# DATALOGGER_CA_ADC_V1.net
KiCad netlist of a schematic drawn in EAGLE
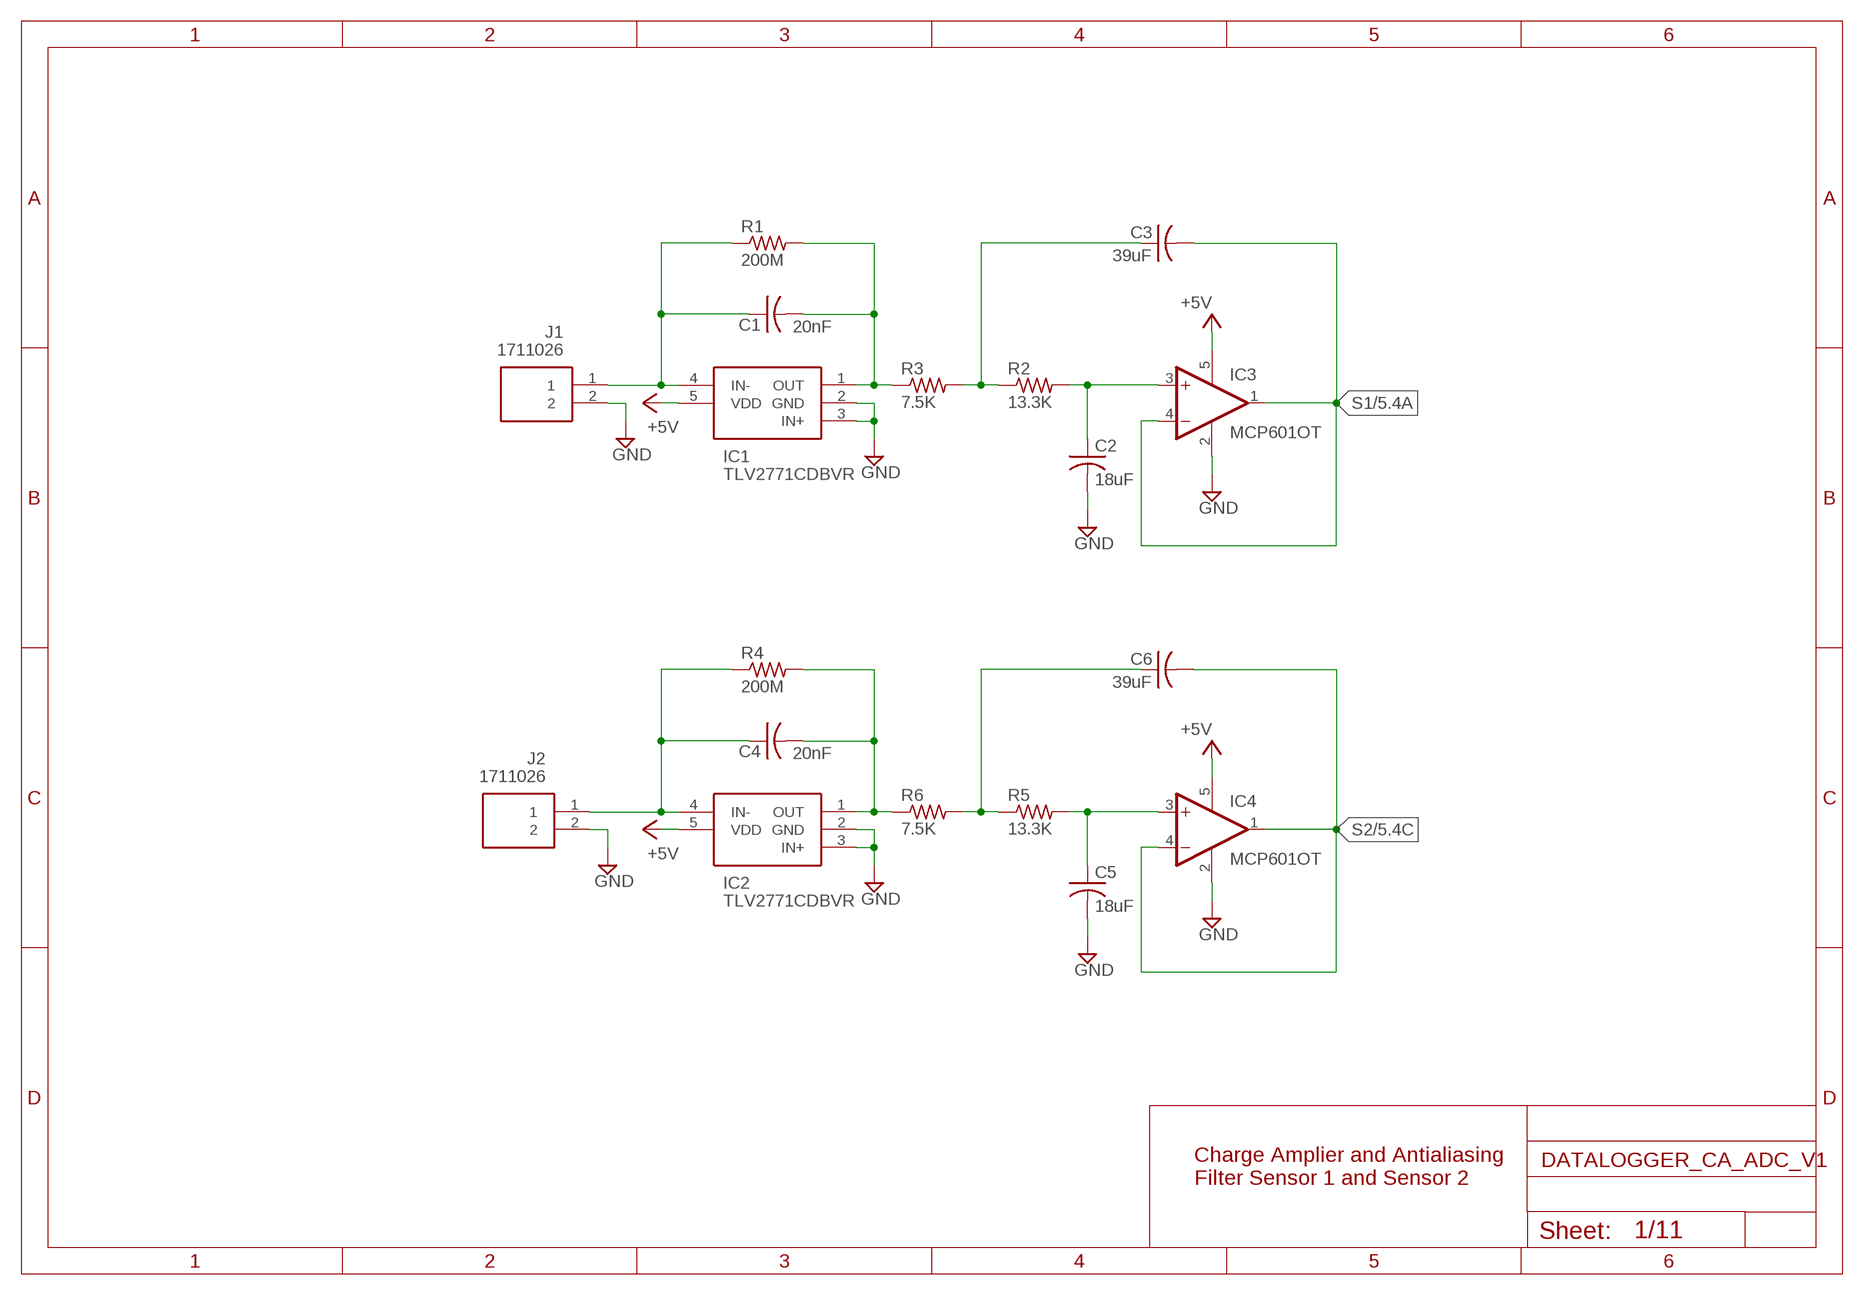
[diagram p0: schematic, sheet 1]
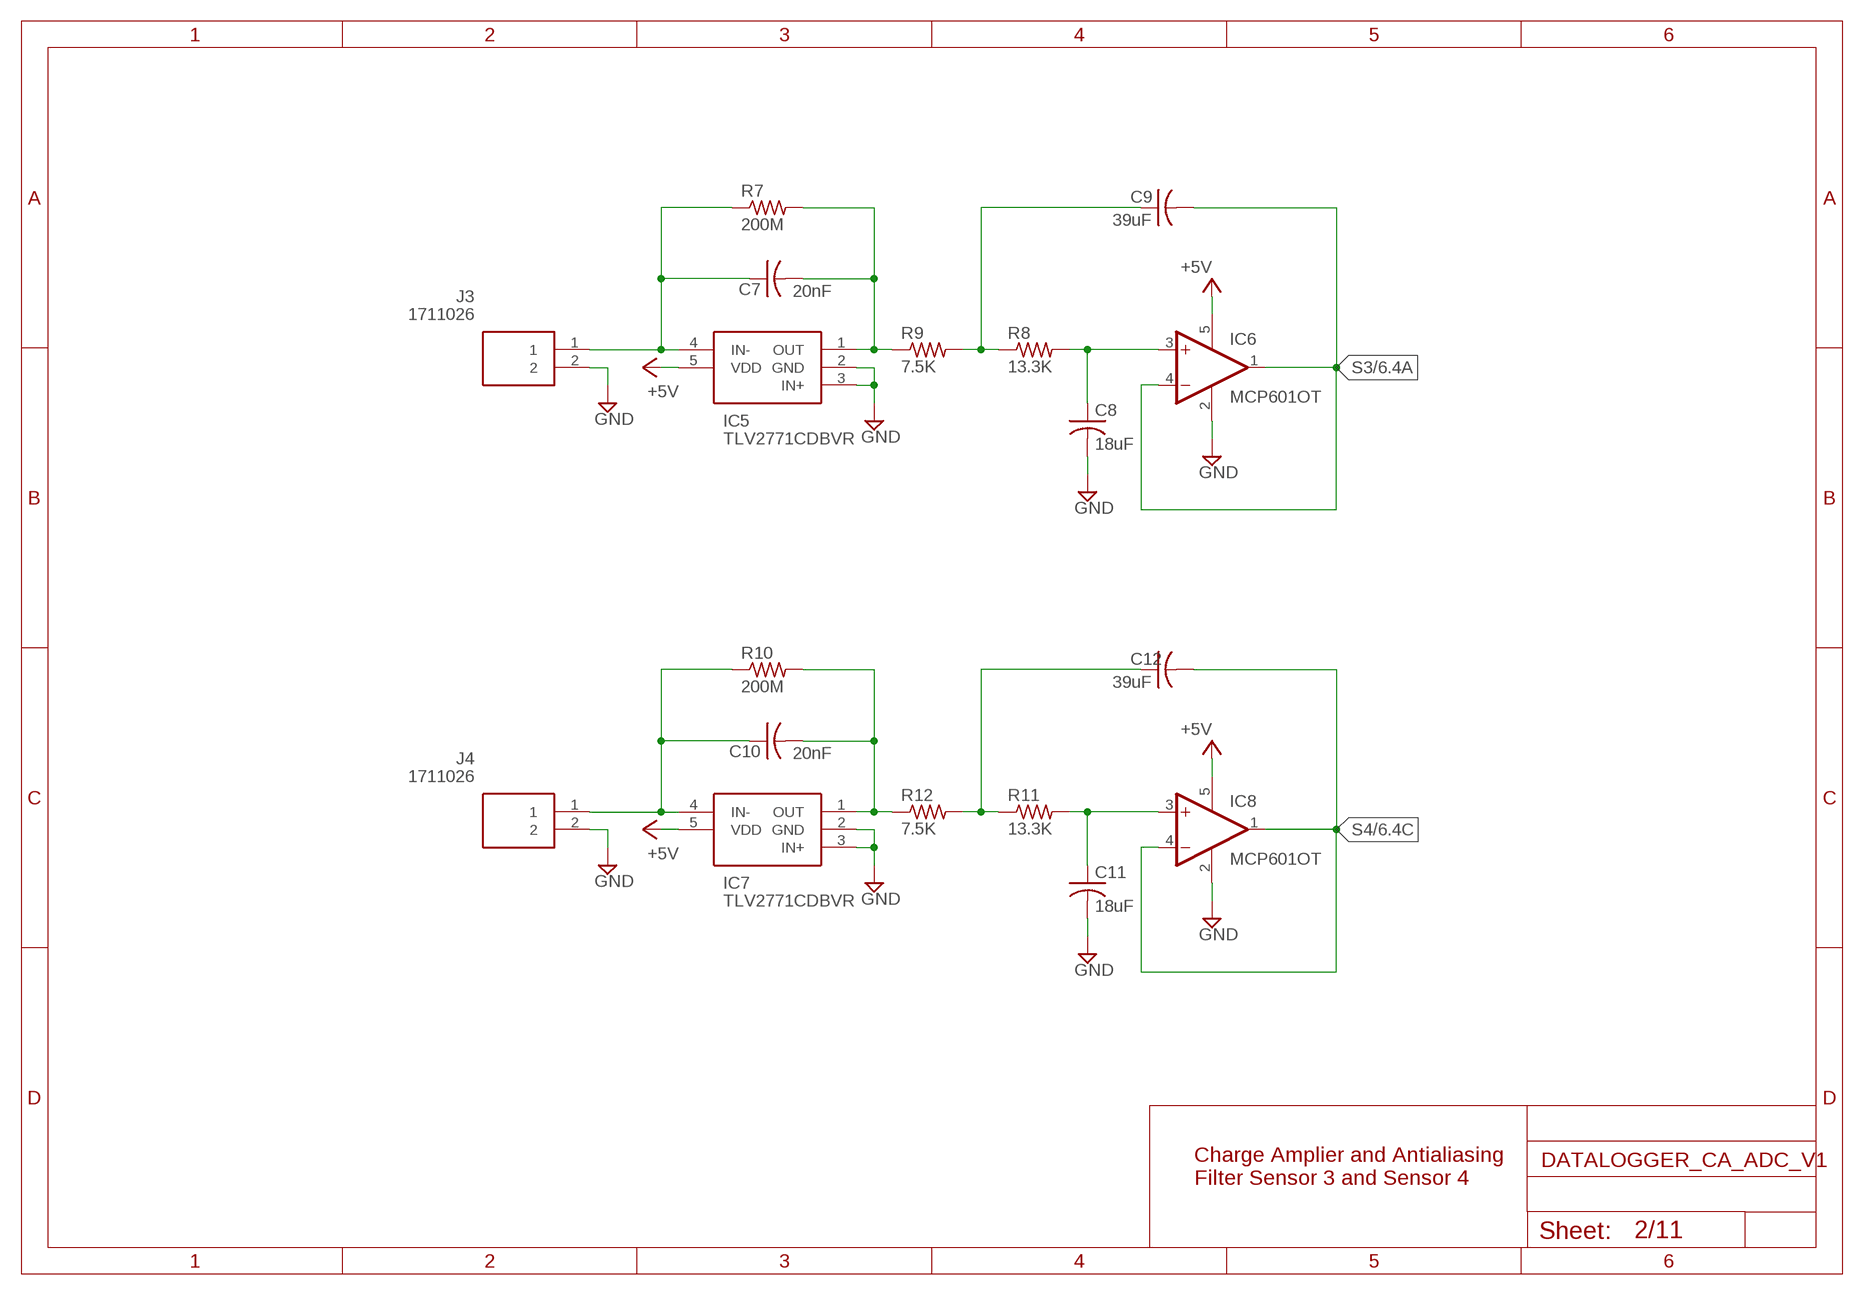
[diagram p1: schematic, sheet 2]
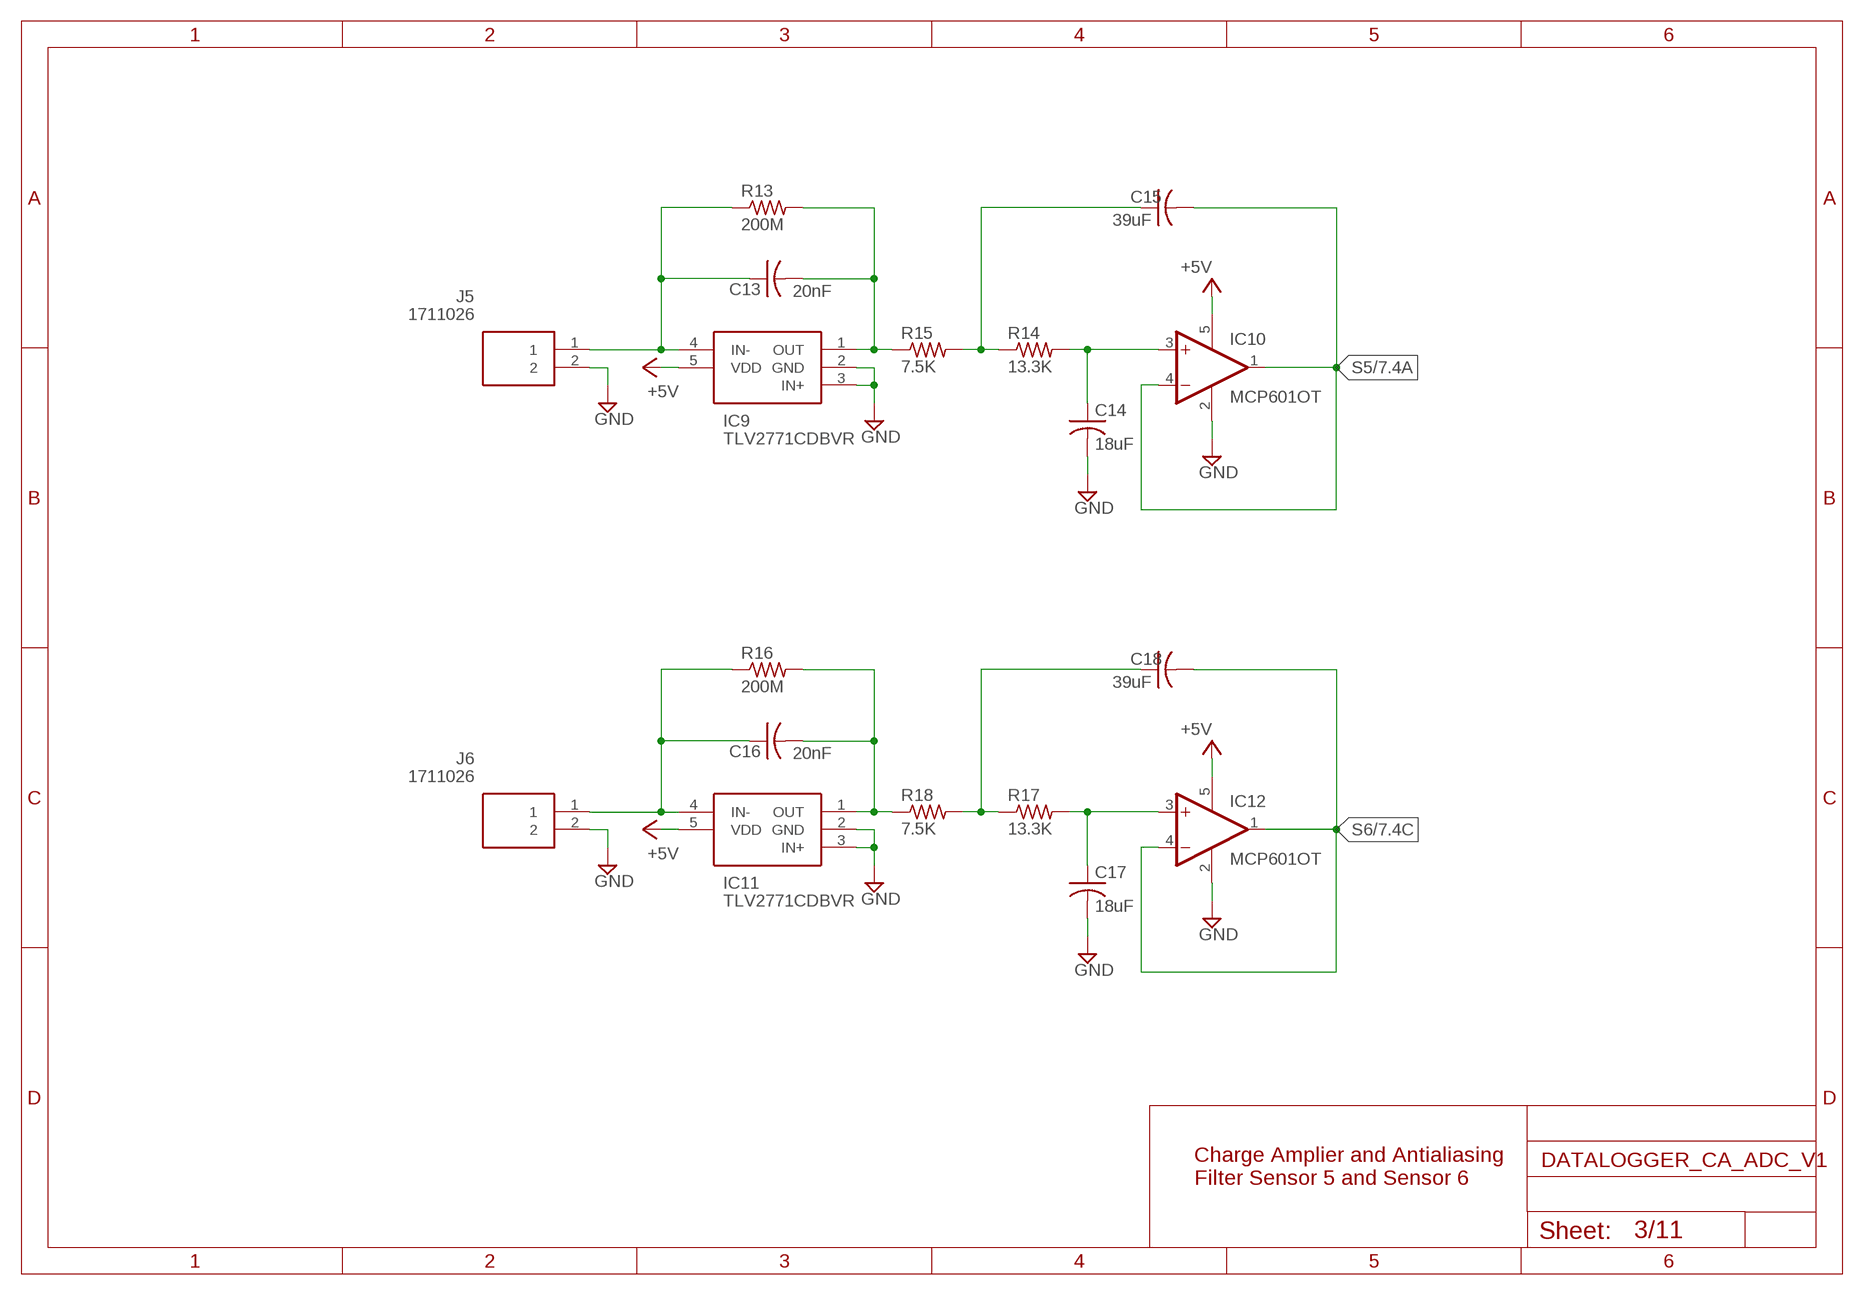
[diagram p2: schematic, sheet 3]
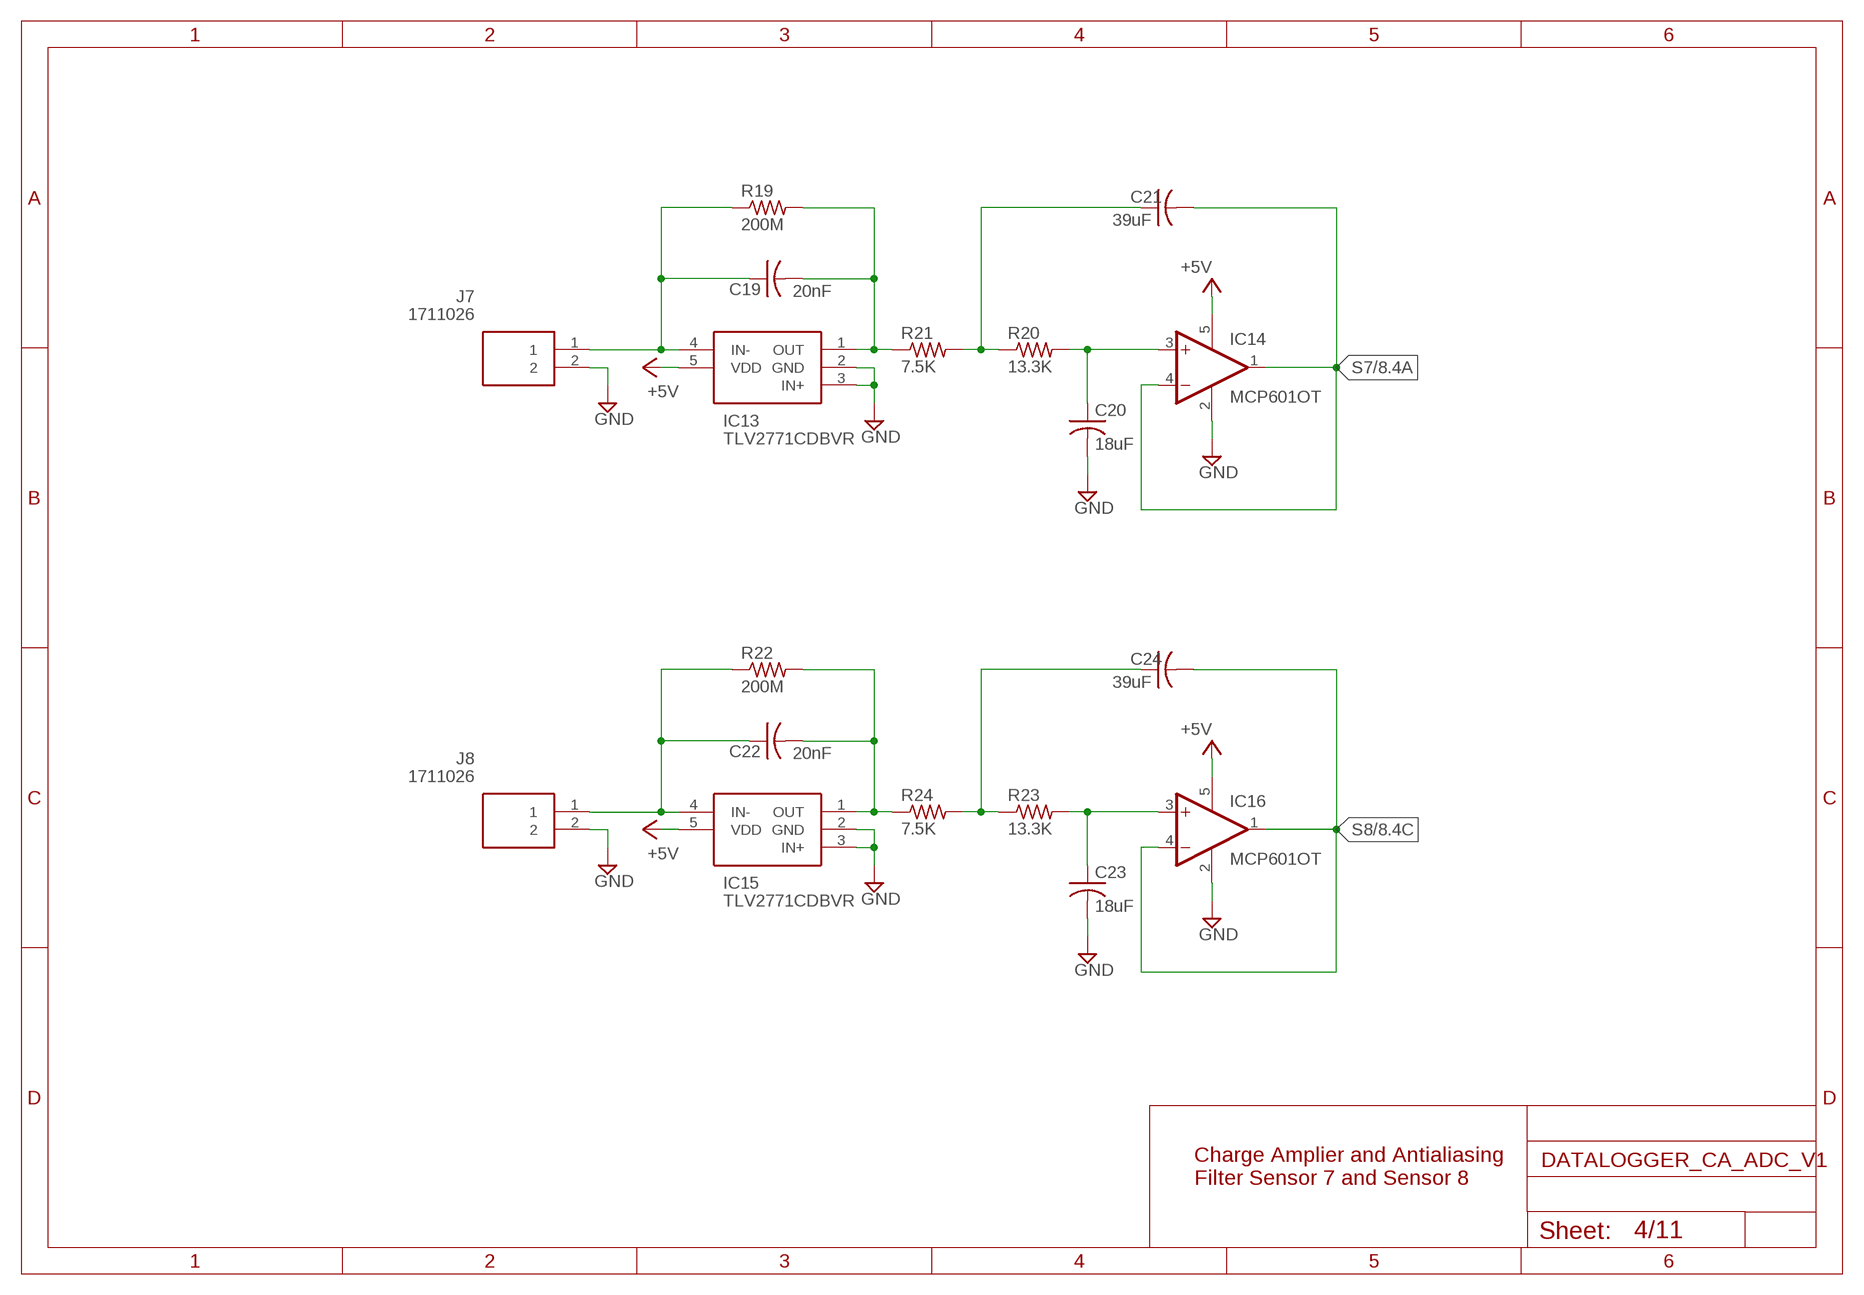
[diagram p3: schematic, sheet 4]
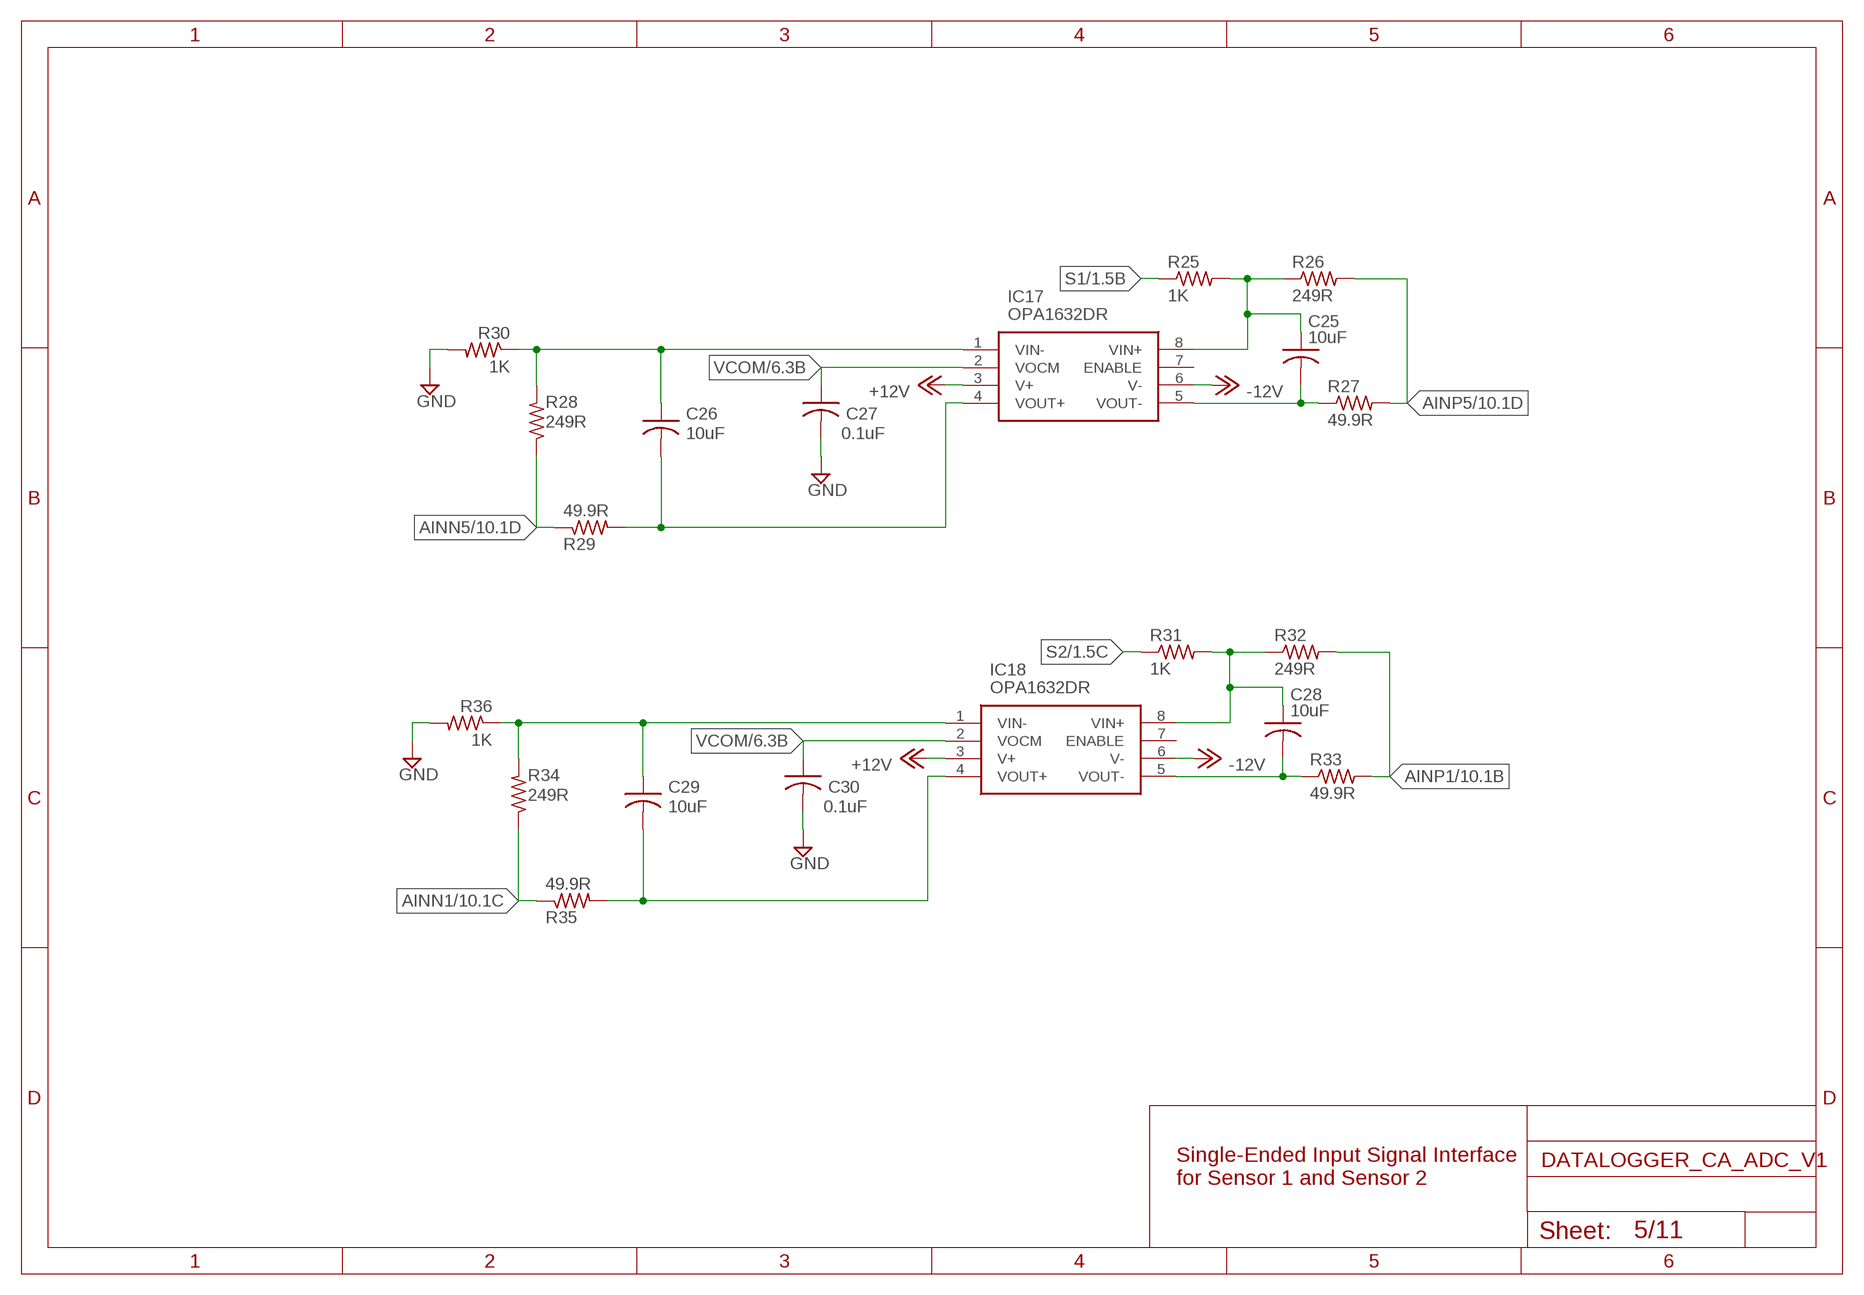
[diagram p4: schematic, sheet 5]
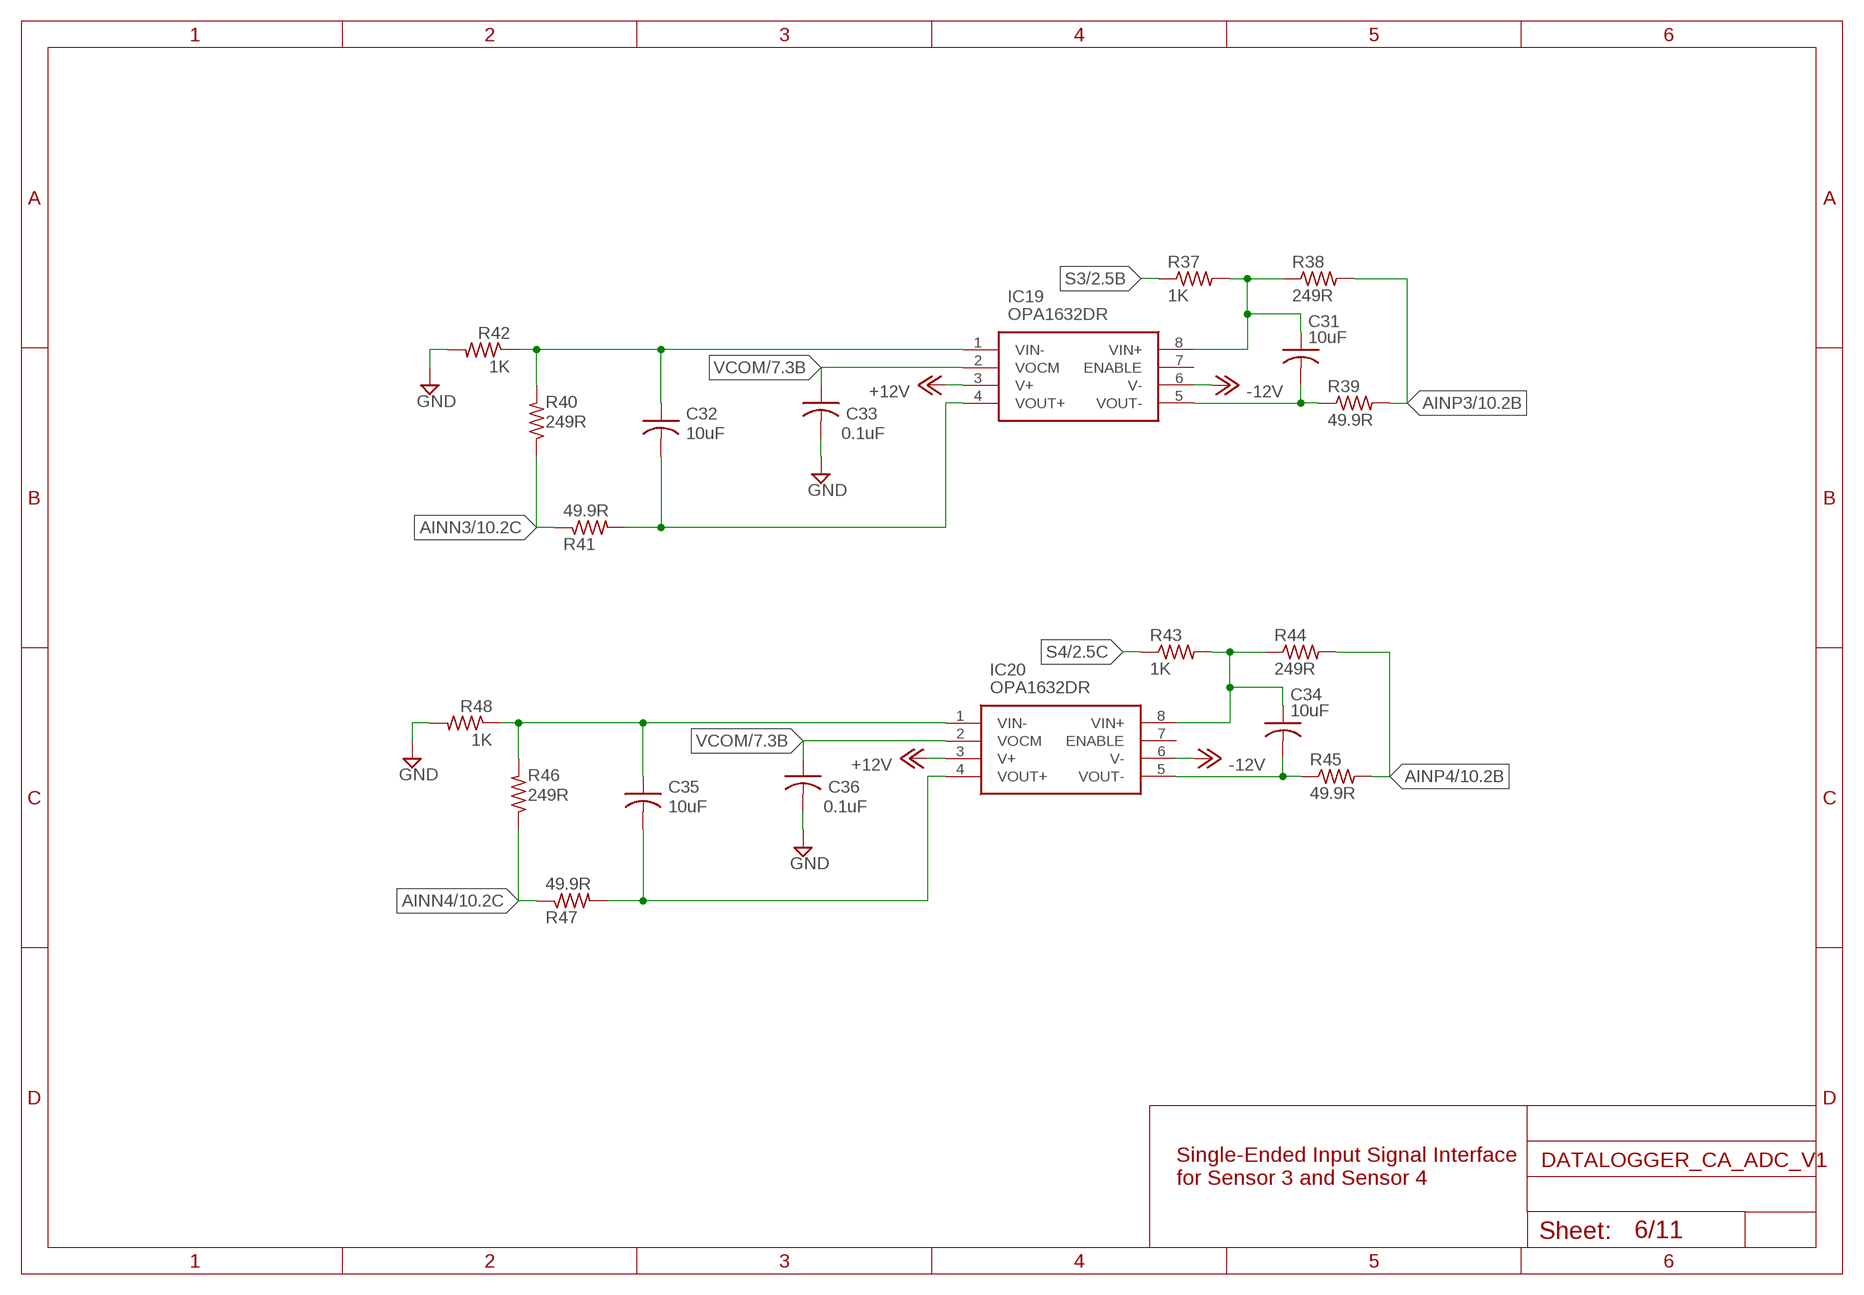
[diagram p5: schematic, sheet 6]
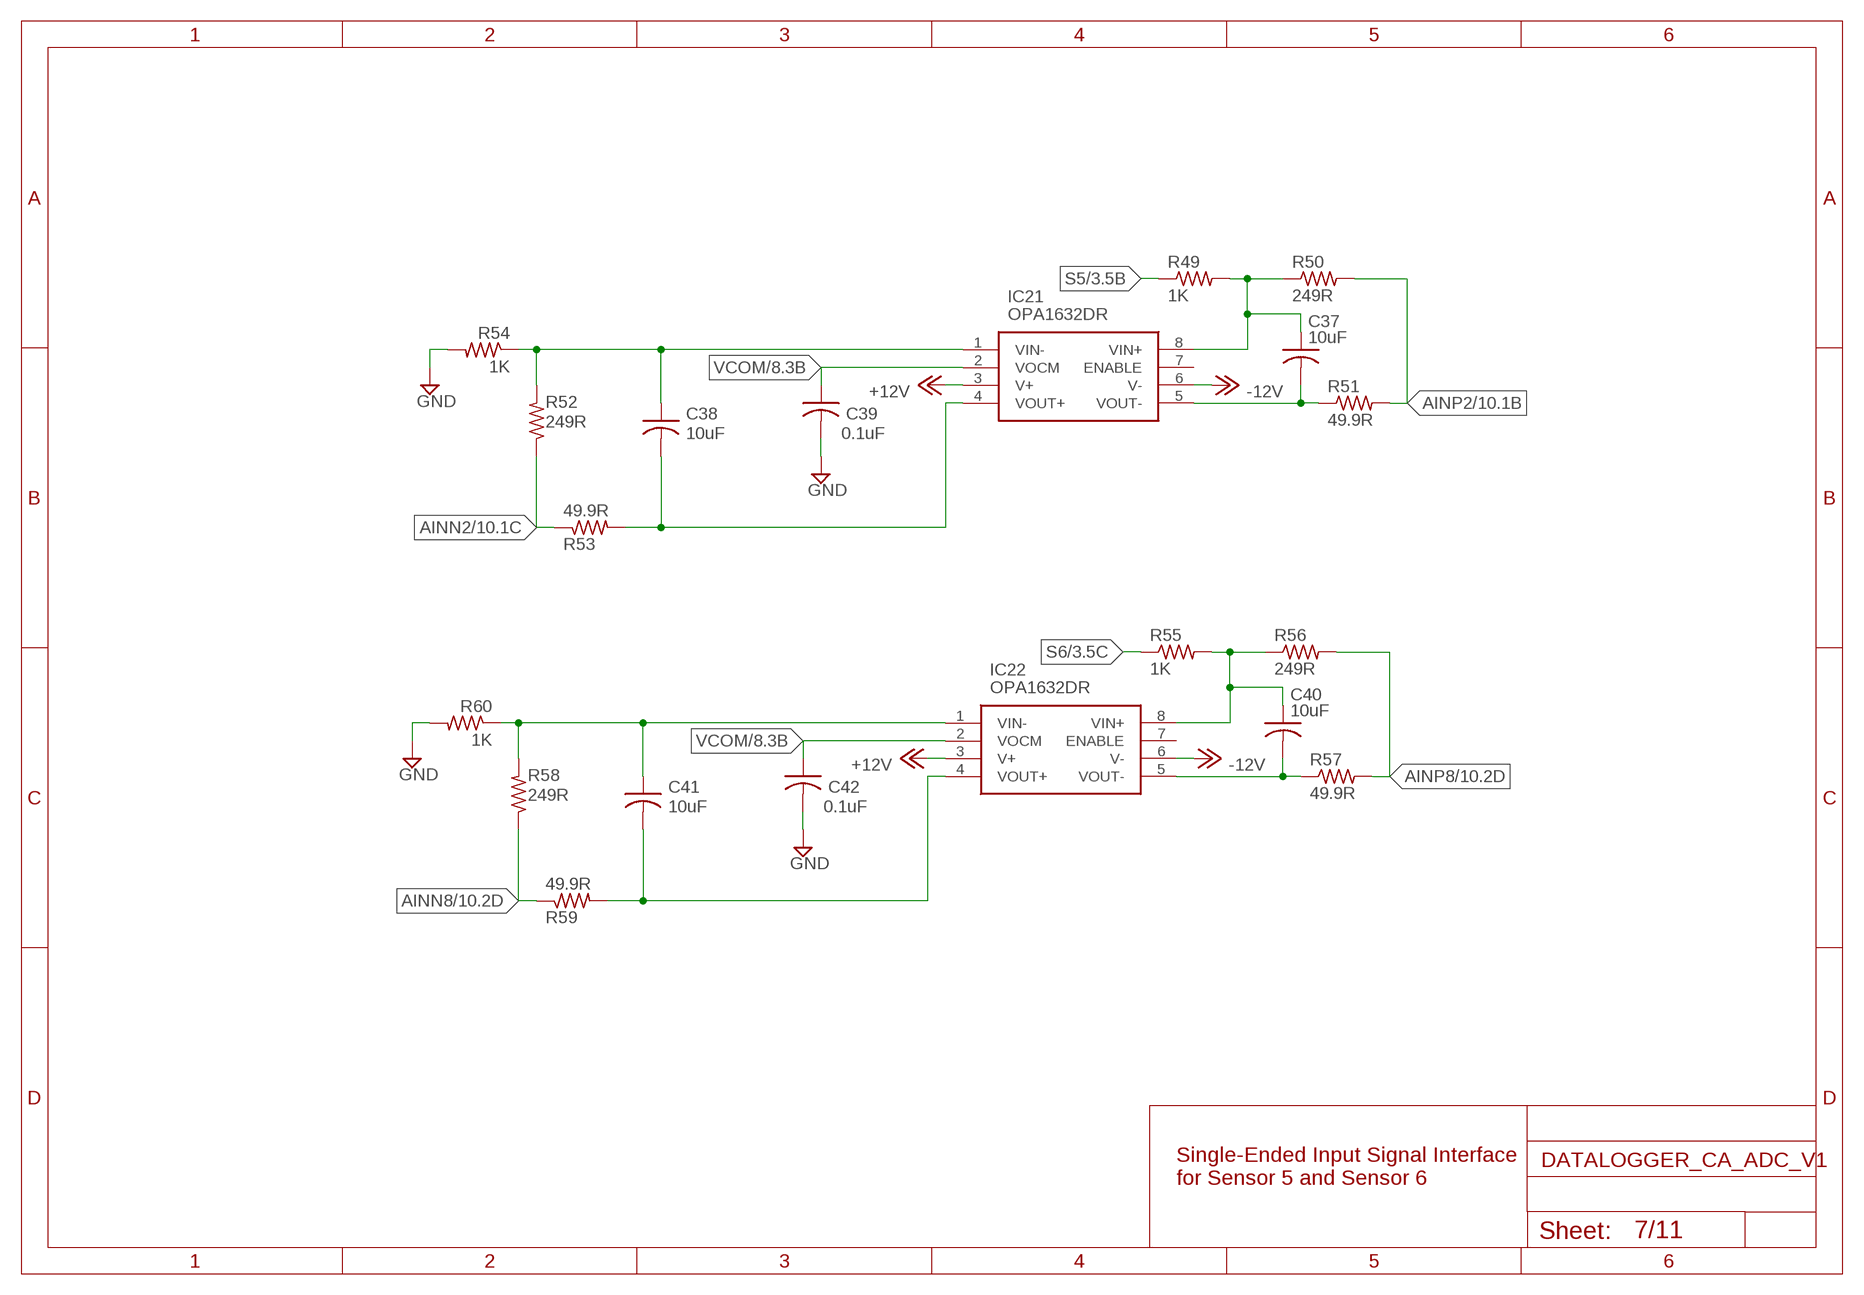
[diagram p6: schematic, sheet 7]
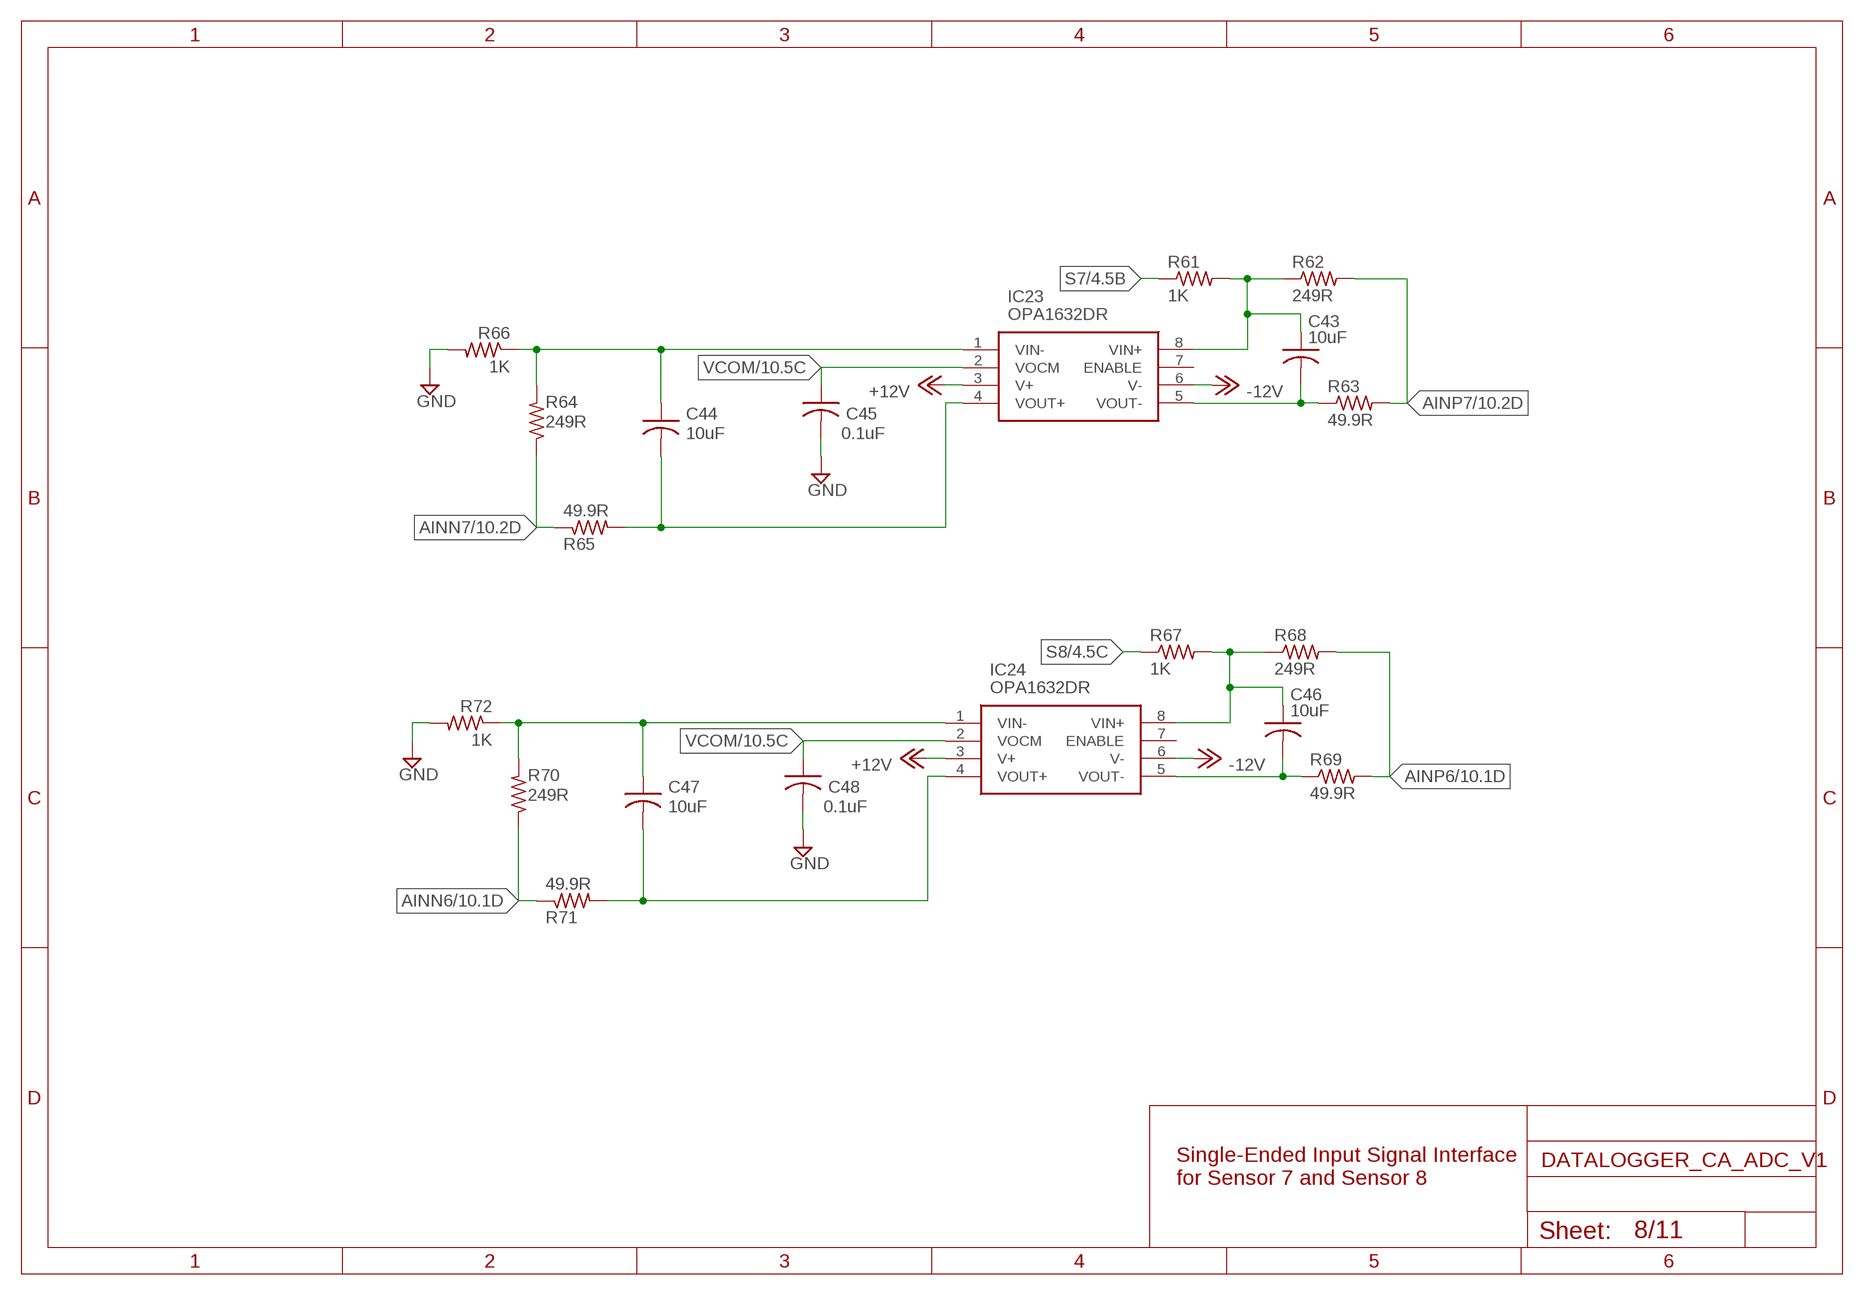
[diagram p7: schematic, sheet 8]
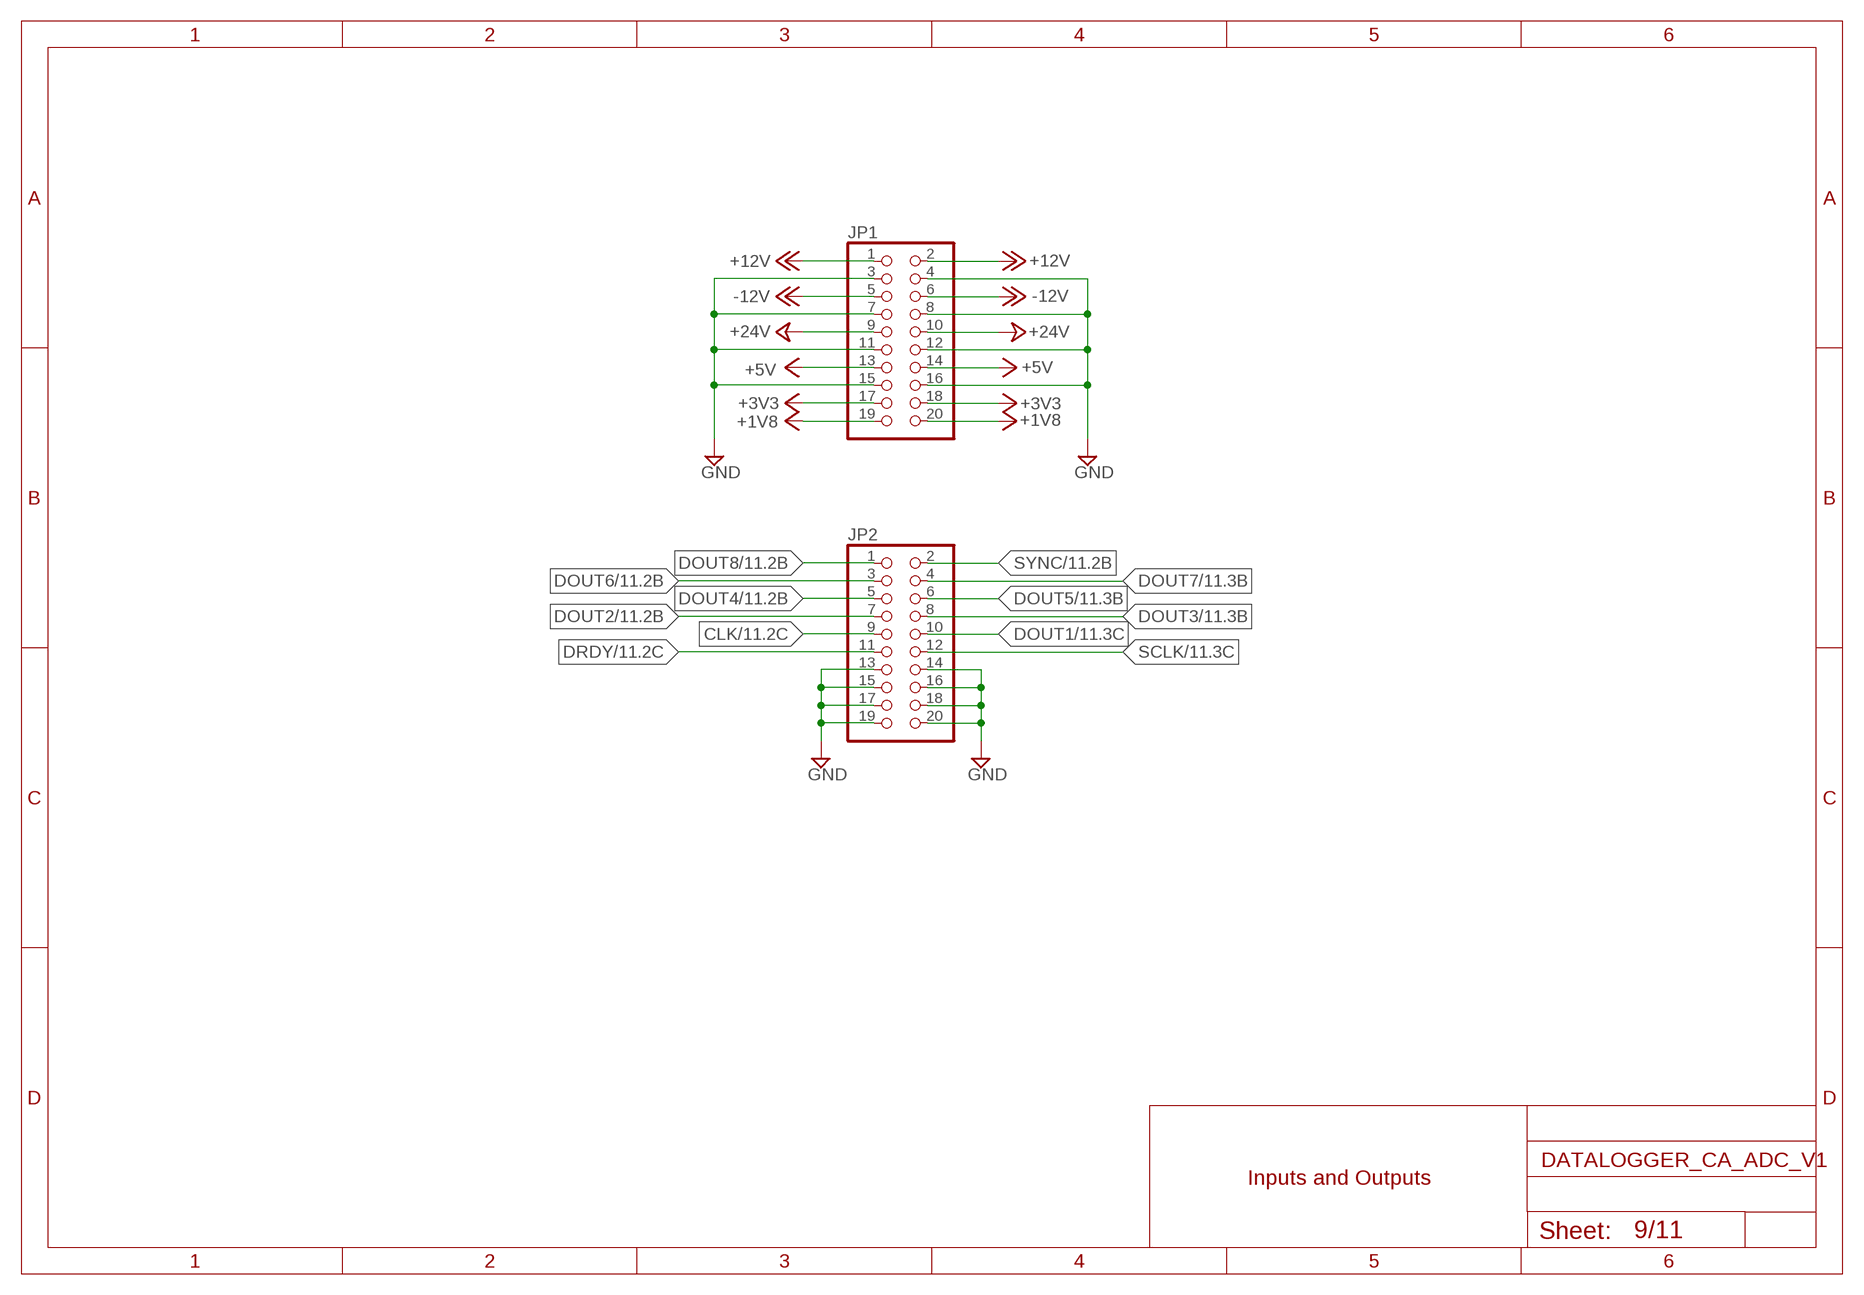
[diagram p8: schematic, sheet 9]
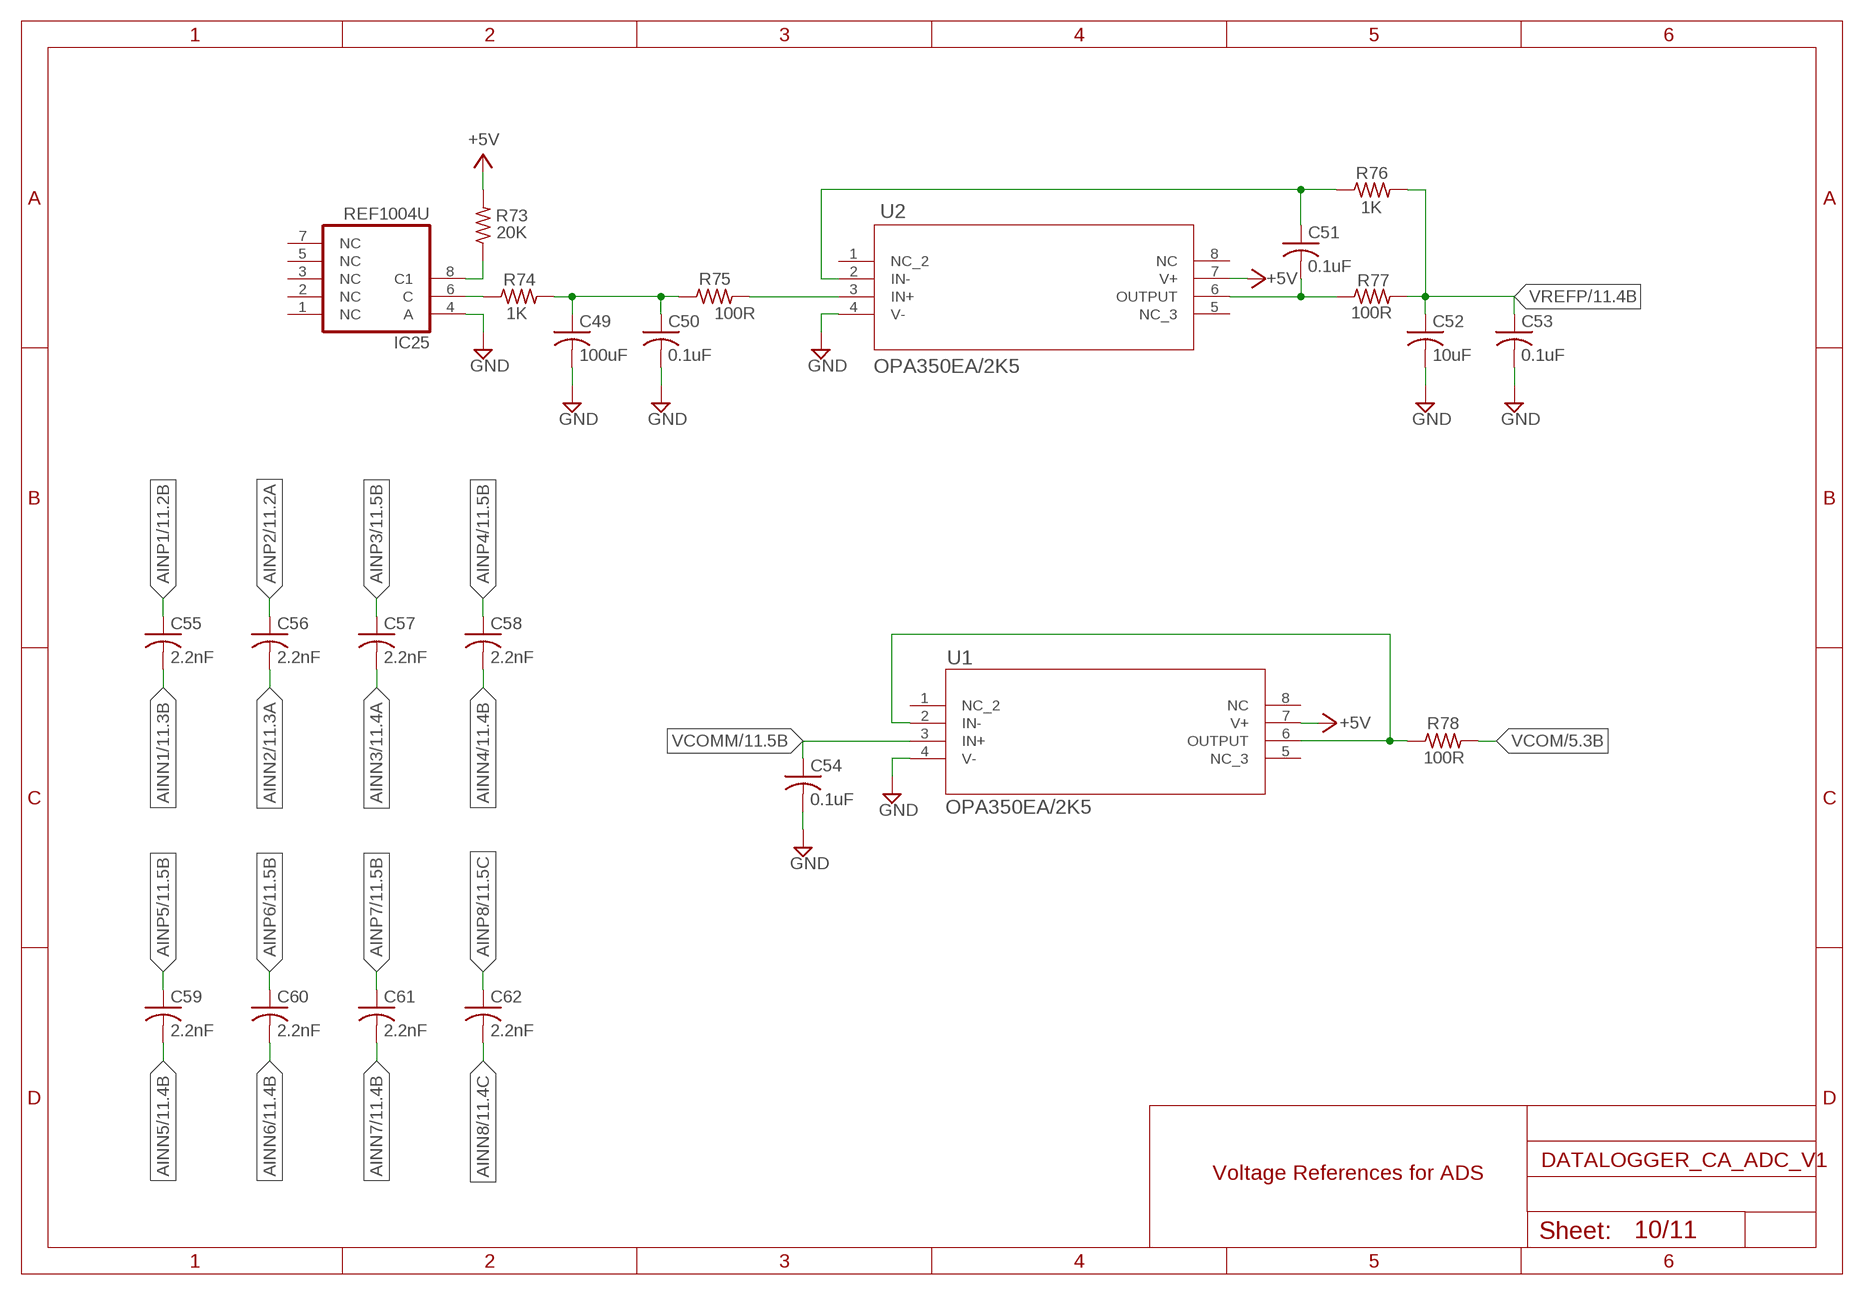
[diagram p9: schematic, sheet 10]
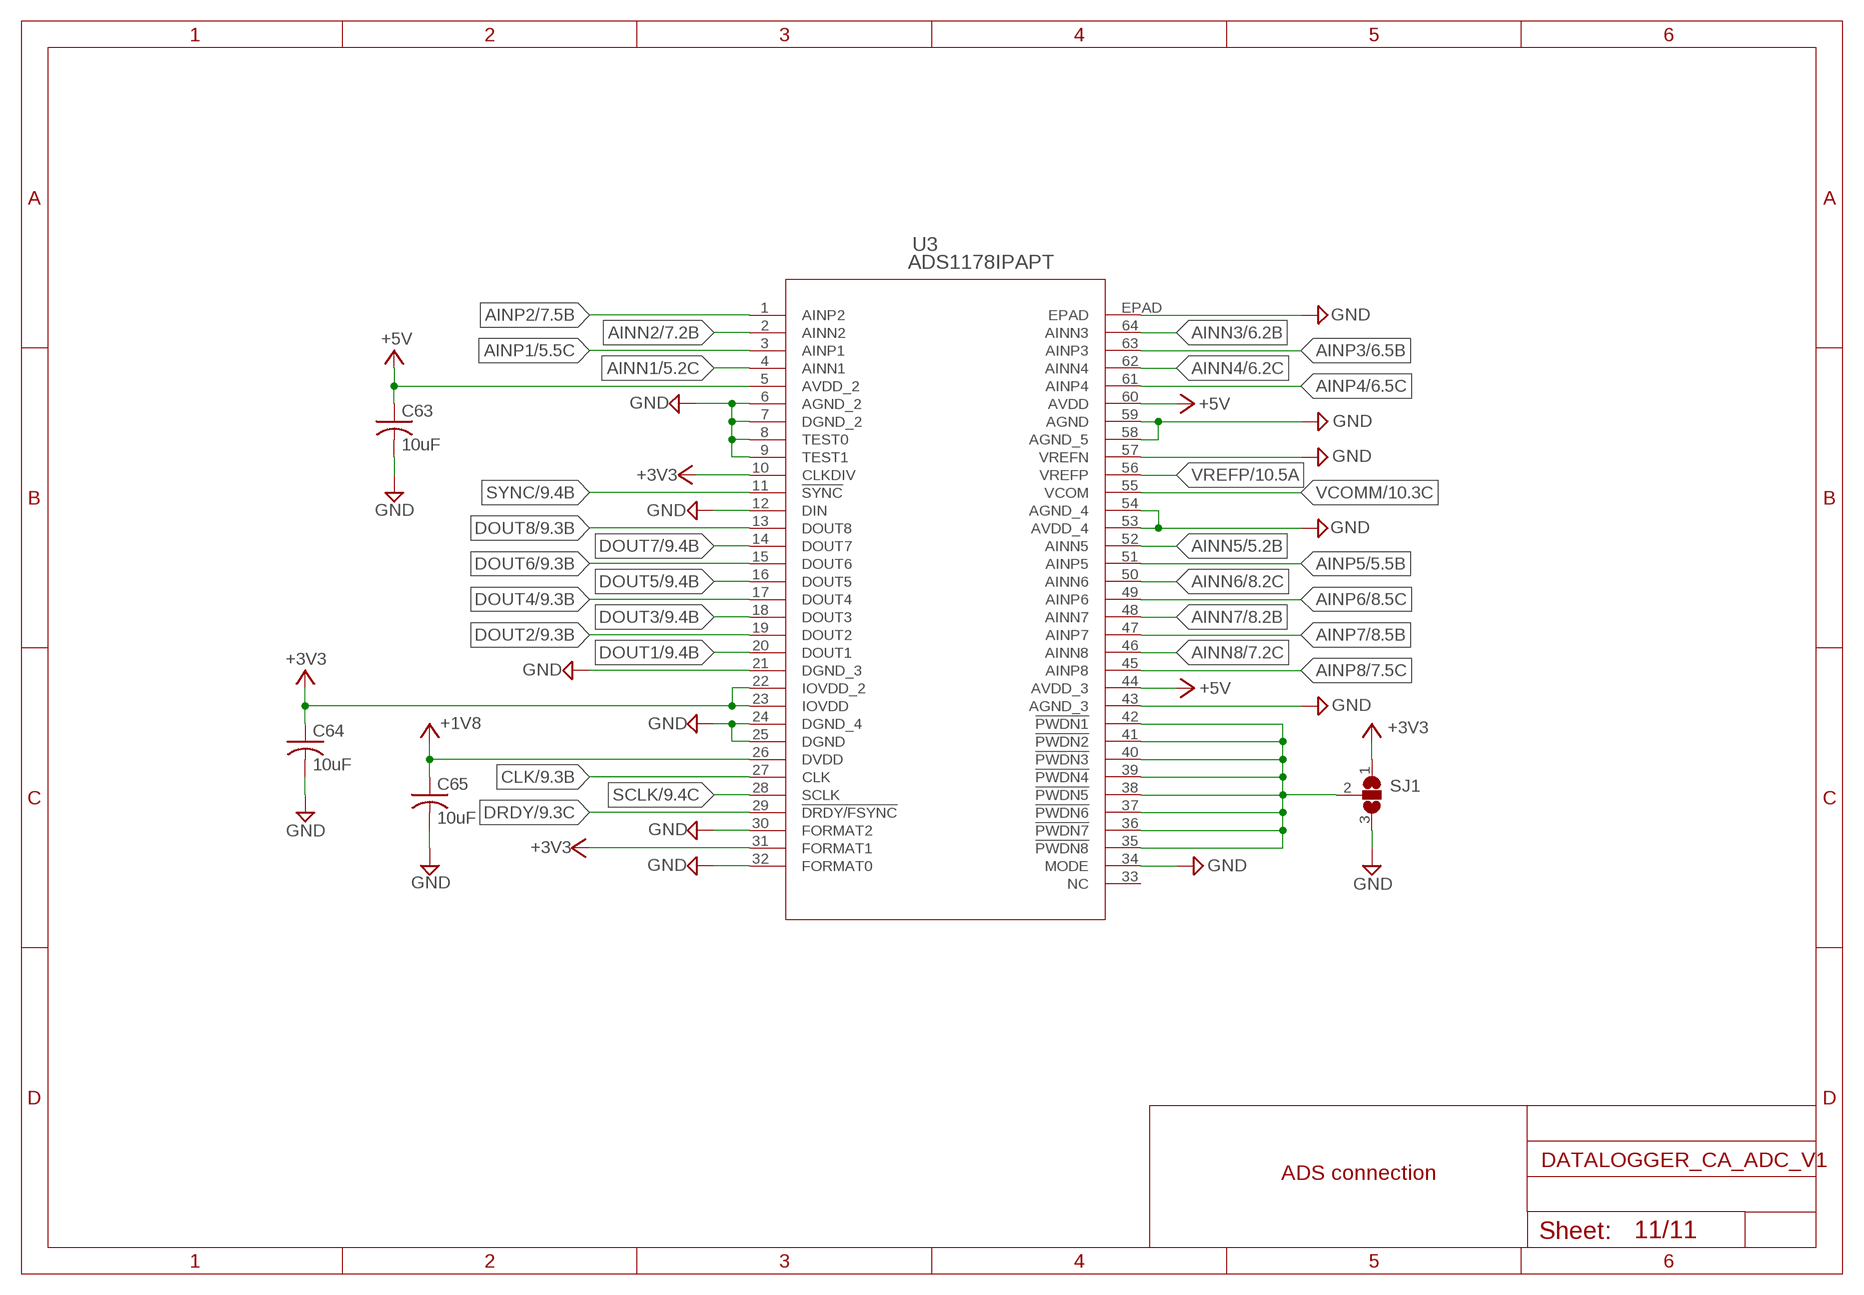
[diagram p10: schematic, sheet 11]

(export (version "E")
  (design (tool "Eeschema 10.0.6"))
  (components
    (comp (ref "C19")
      (value "20nF")
      (footprint "eagle-import:C0805")
      (libsource (lib "eagle-import") (part "C-USC0805"))
    )
    (comp (ref "C20")
      (value "18uF")
      (footprint "eagle-import:C0805")
      (libsource (lib "eagle-import") (part "C-USC0805"))
    )
    (comp (ref "C21")
      (value "39uF")
      (footprint "eagle-import:C0805")
      (libsource (lib "eagle-import") (part "C-USC0805"))
    )
    (comp (ref "C22")
      (value "20nF")
      (footprint "eagle-import:C0805")
      (libsource (lib "eagle-import") (part "C-USC0805"))
    )
    (comp (ref "C23")
      (value "18uF")
      (footprint "eagle-import:C0805")
      (libsource (lib "eagle-import") (part "C-USC0805"))
    )
    (comp (ref "C24")
      (value "39uF")
      (footprint "eagle-import:C0805")
      (libsource (lib "eagle-import") (part "C-USC0805"))
    )
    (comp (ref "IC13")
      (value "TLV2771CDBVR")
      (footprint "eagle-import:SOT95P280X145-5N")
      (fields (field (name "MOUSER_PART_NUMBER") "595-TLV2771CDBVR"))
      (libsource (lib "eagle-import") (part "TLV2771CDBVR"))
    )
    (comp (ref "IC14")
      (value "MCP601OT")
      (footprint "eagle-import:SOT23-5")
      (libsource (lib "eagle-import") (part "MCP601OT"))
    )
    (comp (ref "IC15")
      (value "TLV2771CDBVR")
      (footprint "eagle-import:SOT95P280X145-5N")
      (fields (field (name "MOUSER_PART_NUMBER") "595-TLV2771CDBVR"))
      (libsource (lib "eagle-import") (part "TLV2771CDBVR"))
    )
    (comp (ref "IC16")
      (value "MCP601OT")
      (footprint "eagle-import:SOT23-5")
      (libsource (lib "eagle-import") (part "MCP601OT"))
    )
    (comp (ref "J7")
      (value "1711026")
      (footprint "eagle-import:SHDR2W110P0X500_1X2_1000X1120X")
      (fields (field (name "MOUSER_PART_NUMBER") "651-1711026"))
      (libsource (lib "eagle-import") (part "1711026"))
    )
    (comp (ref "J8")
      (value "1711026")
      (footprint "eagle-import:SHDR2W110P0X500_1X2_1000X1120X")
      (fields (field (name "MOUSER_PART_NUMBER") "651-1711026"))
      (libsource (lib "eagle-import") (part "1711026"))
    )
    (comp (ref "R19")
      (value "200M")
      (footprint "eagle-import:R0805")
      (libsource (lib "eagle-import") (part "R-US_R0805"))
    )
    (comp (ref "R20")
      (value "13.3K")
      (footprint "eagle-import:R0805")
      (libsource (lib "eagle-import") (part "R-US_R0805"))
    )
    (comp (ref "R21")
      (value "7.5K")
      (footprint "eagle-import:R0805")
      (libsource (lib "eagle-import") (part "R-US_R0805"))
    )
    (comp (ref "R22")
      (value "200M")
      (footprint "eagle-import:R0805")
      (libsource (lib "eagle-import") (part "R-US_R0805"))
    )
    (comp (ref "R23")
      (value "13.3K")
      (footprint "eagle-import:R0805")
      (libsource (lib "eagle-import") (part "R-US_R0805"))
    )
    (comp (ref "R24")
      (value "7.5K")
      (footprint "eagle-import:R0805")
      (libsource (lib "eagle-import") (part "R-US_R0805"))
    )
    (comp (ref "C37")
      (value "10uF")
      (footprint "eagle-import:C0805")
      (libsource (lib "eagle-import") (part "C-USC0805"))
    )
    (comp (ref "C38")
      (value "10uF")
      (footprint "eagle-import:C0805")
      (libsource (lib "eagle-import") (part "C-USC0805"))
    )
    (comp (ref "C39")
      (value "0.1uF")
      (footprint "eagle-import:C0805")
      (libsource (lib "eagle-import") (part "C-USC0805"))
    )
    (comp (ref "C40")
      (value "10uF")
      (footprint "eagle-import:C0805")
      (libsource (lib "eagle-import") (part "C-USC0805"))
    )
    (comp (ref "C41")
      (value "10uF")
      (footprint "eagle-import:C0805")
      (libsource (lib "eagle-import") (part "C-USC0805"))
    )
    (comp (ref "C42")
      (value "0.1uF")
      (footprint "eagle-import:C0805")
      (libsource (lib "eagle-import") (part "C-USC0805"))
    )
    (comp (ref "IC21")
      (value "OPA1632DR")
      (footprint "eagle-import:SOIC127P600X175-8N")
      (fields (field (name "MOUSER_PART_NUMBER") "595-OPA1632DR"))
      (libsource (lib "eagle-import") (part "OPA1632DR"))
    )
    (comp (ref "IC22")
      (value "OPA1632DR")
      (footprint "eagle-import:SOIC127P600X175-8N")
      (fields (field (name "MOUSER_PART_NUMBER") "595-OPA1632DR"))
      (libsource (lib "eagle-import") (part "OPA1632DR"))
    )
    (comp (ref "R49")
      (value "1K")
      (footprint "eagle-import:R0805")
      (libsource (lib "eagle-import") (part "R-US_R0805"))
    )
    (comp (ref "R50")
      (value "249R")
      (footprint "eagle-import:R0805")
      (libsource (lib "eagle-import") (part "R-US_R0805"))
    )
    (comp (ref "R51")
      (value "49.9R")
      (footprint "eagle-import:R0805")
      (libsource (lib "eagle-import") (part "R-US_R0805"))
    )
    (comp (ref "R52")
      (value "249R")
      (footprint "eagle-import:R0805")
      (libsource (lib "eagle-import") (part "R-US_R0805"))
    )
    (comp (ref "R53")
      (value "49.9R")
      (footprint "eagle-import:R0805")
      (libsource (lib "eagle-import") (part "R-US_R0805"))
    )
    (comp (ref "R54")
      (value "1K")
      (footprint "eagle-import:R0805")
      (libsource (lib "eagle-import") (part "R-US_R0805"))
    )
    (comp (ref "R55")
      (value "1K")
      (footprint "eagle-import:R0805")
      (libsource (lib "eagle-import") (part "R-US_R0805"))
    )
    (comp (ref "R56")
      (value "249R")
      (footprint "eagle-import:R0805")
      (libsource (lib "eagle-import") (part "R-US_R0805"))
    )
    (comp (ref "R57")
      (value "49.9R")
      (footprint "eagle-import:R0805")
      (libsource (lib "eagle-import") (part "R-US_R0805"))
    )
    (comp (ref "R58")
      (value "249R")
      (footprint "eagle-import:R0805")
      (libsource (lib "eagle-import") (part "R-US_R0805"))
    )
    (comp (ref "R59")
      (value "49.9R")
      (footprint "eagle-import:R0805")
      (libsource (lib "eagle-import") (part "R-US_R0805"))
    )
    (comp (ref "R60")
      (value "1K")
      (footprint "eagle-import:R0805")
      (libsource (lib "eagle-import") (part "R-US_R0805"))
    )
    (comp (ref "C7")
      (value "20nF")
      (footprint "eagle-import:C0805")
      (libsource (lib "eagle-import") (part "C-USC0805"))
    )
    (comp (ref "C8")
      (value "18uF")
      (footprint "eagle-import:C0805")
      (libsource (lib "eagle-import") (part "C-USC0805"))
    )
    (comp (ref "C9")
      (value "39uF")
      (footprint "eagle-import:C0805")
      (libsource (lib "eagle-import") (part "C-USC0805"))
    )
    (comp (ref "C10")
      (value "20nF")
      (footprint "eagle-import:C0805")
      (libsource (lib "eagle-import") (part "C-USC0805"))
    )
    (comp (ref "C11")
      (value "18uF")
      (footprint "eagle-import:C0805")
      (libsource (lib "eagle-import") (part "C-USC0805"))
    )
    (comp (ref "C12")
      (value "39uF")
      (footprint "eagle-import:C0805")
      (libsource (lib "eagle-import") (part "C-USC0805"))
    )
    (comp (ref "IC5")
      (value "TLV2771CDBVR")
      (footprint "eagle-import:SOT95P280X145-5N")
      (fields (field (name "MOUSER_PART_NUMBER") "595-TLV2771CDBVR"))
      (libsource (lib "eagle-import") (part "TLV2771CDBVR"))
    )
    (comp (ref "IC6")
      (value "MCP601OT")
      (footprint "eagle-import:SOT23-5")
      (libsource (lib "eagle-import") (part "MCP601OT"))
    )
    (comp (ref "IC7")
      (value "TLV2771CDBVR")
      (footprint "eagle-import:SOT95P280X145-5N")
      (fields (field (name "MOUSER_PART_NUMBER") "595-TLV2771CDBVR"))
      (libsource (lib "eagle-import") (part "TLV2771CDBVR"))
    )
    (comp (ref "IC8")
      (value "MCP601OT")
      (footprint "eagle-import:SOT23-5")
      (libsource (lib "eagle-import") (part "MCP601OT"))
    )
    (comp (ref "J3")
      (value "1711026")
      (footprint "eagle-import:SHDR2W110P0X500_1X2_1000X1120X")
      (fields (field (name "MOUSER_PART_NUMBER") "651-1711026"))
      (libsource (lib "eagle-import") (part "1711026"))
    )
    (comp (ref "J4")
      (value "1711026")
      (footprint "eagle-import:SHDR2W110P0X500_1X2_1000X1120X")
      (fields (field (name "MOUSER_PART_NUMBER") "651-1711026"))
      (libsource (lib "eagle-import") (part "1711026"))
    )
    (comp (ref "R7")
      (value "200M")
      (footprint "eagle-import:R0805")
      (libsource (lib "eagle-import") (part "R-US_R0805"))
    )
    (comp (ref "R8")
      (value "13.3K")
      (footprint "eagle-import:R0805")
      (libsource (lib "eagle-import") (part "R-US_R0805"))
    )
    (comp (ref "R9")
      (value "7.5K")
      (footprint "eagle-import:R0805")
      (libsource (lib "eagle-import") (part "R-US_R0805"))
    )
    (comp (ref "R10")
      (value "200M")
      (footprint "eagle-import:R0805")
      (libsource (lib "eagle-import") (part "R-US_R0805"))
    )
    (comp (ref "R11")
      (value "13.3K")
      (footprint "eagle-import:R0805")
      (libsource (lib "eagle-import") (part "R-US_R0805"))
    )
    (comp (ref "R12")
      (value "7.5K")
      (footprint "eagle-import:R0805")
      (libsource (lib "eagle-import") (part "R-US_R0805"))
    )
    (comp (ref "C25")
      (value "10uF")
      (footprint "eagle-import:C0805")
      (libsource (lib "eagle-import") (part "C-USC0805"))
    )
    (comp (ref "C26")
      (value "10uF")
      (footprint "eagle-import:C0805")
      (libsource (lib "eagle-import") (part "C-USC0805"))
    )
    (comp (ref "C27")
      (value "0.1uF")
      (footprint "eagle-import:C0805")
      (libsource (lib "eagle-import") (part "C-USC0805"))
    )
    (comp (ref "C28")
      (value "10uF")
      (footprint "eagle-import:C0805")
      (libsource (lib "eagle-import") (part "C-USC0805"))
    )
    (comp (ref "C29")
      (value "10uF")
      (footprint "eagle-import:C0805")
      (libsource (lib "eagle-import") (part "C-USC0805"))
    )
    (comp (ref "C30")
      (value "0.1uF")
      (footprint "eagle-import:C0805")
      (libsource (lib "eagle-import") (part "C-USC0805"))
    )
    (comp (ref "IC17")
      (value "OPA1632DR")
      (footprint "eagle-import:SOIC127P600X175-8N")
      (fields (field (name "MOUSER_PART_NUMBER") "595-OPA1632DR"))
      (libsource (lib "eagle-import") (part "OPA1632DR"))
    )
    (comp (ref "IC18")
      (value "OPA1632DR")
      (footprint "eagle-import:SOIC127P600X175-8N")
      (fields (field (name "MOUSER_PART_NUMBER") "595-OPA1632DR"))
      (libsource (lib "eagle-import") (part "OPA1632DR"))
    )
    (comp (ref "R25")
      (value "1K")
      (footprint "eagle-import:R0805")
      (libsource (lib "eagle-import") (part "R-US_R0805"))
    )
    (comp (ref "R26")
      (value "249R")
      (footprint "eagle-import:R0805")
      (libsource (lib "eagle-import") (part "R-US_R0805"))
    )
    (comp (ref "R27")
      (value "49.9R")
      (footprint "eagle-import:R0805")
      (libsource (lib "eagle-import") (part "R-US_R0805"))
    )
    (comp (ref "R28")
      (value "249R")
      (footprint "eagle-import:R0805")
      (libsource (lib "eagle-import") (part "R-US_R0805"))
    )
    (comp (ref "R29")
      (value "49.9R")
      (footprint "eagle-import:R0805")
      (libsource (lib "eagle-import") (part "R-US_R0805"))
    )
    (comp (ref "R30")
      (value "1K")
      (footprint "eagle-import:R0805")
      (libsource (lib "eagle-import") (part "R-US_R0805"))
    )
    (comp (ref "R31")
      (value "1K")
      (footprint "eagle-import:R0805")
      (libsource (lib "eagle-import") (part "R-US_R0805"))
    )
    (comp (ref "R32")
      (value "249R")
      (footprint "eagle-import:R0805")
      (libsource (lib "eagle-import") (part "R-US_R0805"))
    )
    (comp (ref "R33")
      (value "49.9R")
      (footprint "eagle-import:R0805")
      (libsource (lib "eagle-import") (part "R-US_R0805"))
    )
    (comp (ref "R34")
      (value "249R")
      (footprint "eagle-import:R0805")
      (libsource (lib "eagle-import") (part "R-US_R0805"))
    )
    (comp (ref "R35")
      (value "49.9R")
      (footprint "eagle-import:R0805")
      (libsource (lib "eagle-import") (part "R-US_R0805"))
    )
    (comp (ref "R36")
      (value "1K")
      (footprint "eagle-import:R0805")
      (libsource (lib "eagle-import") (part "R-US_R0805"))
    )
    (comp (ref "C63")
      (value "10uF")
      (footprint "eagle-import:C0805")
      (libsource (lib "eagle-import") (part "C-USC0805"))
    )
    (comp (ref "C64")
      (value "10uF")
      (footprint "eagle-import:C0805")
      (libsource (lib "eagle-import") (part "C-USC0805"))
    )
    (comp (ref "C65")
      (value "10uF")
      (footprint "eagle-import:C0805")
      (libsource (lib "eagle-import") (part "C-USC0805"))
    )
    (comp (ref "SJ1")
      (value "SJ2W")
      (footprint "eagle-import:SJ_2")
      (libsource (lib "eagle-import") (part "SJ2W"))
    )
    (comp (ref "U3")
      (value "ADS1178IPAPT")
      (footprint "eagle-import:PAP64_TEX")
      (libsource (lib "eagle-import") (part "ADS1178IPAPT"))
    )
    (comp (ref "C49")
      (value "100uF")
      (footprint "eagle-import:C1206")
      (libsource (lib "eagle-import") (part "C-USC1206"))
    )
    (comp (ref "C50")
      (value "0.1uF")
      (footprint "eagle-import:C0805")
      (libsource (lib "eagle-import") (part "C-USC0805"))
    )
    (comp (ref "C51")
      (value "0.1uF")
      (footprint "eagle-import:C0805")
      (libsource (lib "eagle-import") (part "C-USC0805"))
    )
    (comp (ref "C52")
      (value "10uF")
      (footprint "eagle-import:C0805")
      (libsource (lib "eagle-import") (part "C-USC0805"))
    )
    (comp (ref "C53")
      (value "0.1uF")
      (footprint "eagle-import:C0805")
      (libsource (lib "eagle-import") (part "C-USC0805"))
    )
    (comp (ref "C54")
      (value "0.1uF")
      (footprint "eagle-import:C0805")
      (libsource (lib "eagle-import") (part "C-USC0805"))
    )
    (comp (ref "C55")
      (value "2.2nF")
      (footprint "eagle-import:C0805")
      (libsource (lib "eagle-import") (part "C-USC0805"))
    )
    (comp (ref "C56")
      (value "2.2nF")
      (footprint "eagle-import:C0805")
      (libsource (lib "eagle-import") (part "C-USC0805"))
    )
    (comp (ref "C57")
      (value "2.2nF")
      (footprint "eagle-import:C0805")
      (libsource (lib "eagle-import") (part "C-USC0805"))
    )
    (comp (ref "C58")
      (value "2.2nF")
      (footprint "eagle-import:C0805")
      (libsource (lib "eagle-import") (part "C-USC0805"))
    )
    (comp (ref "C59")
      (value "2.2nF")
      (footprint "eagle-import:C0805")
      (libsource (lib "eagle-import") (part "C-USC0805"))
    )
    (comp (ref "C60")
      (value "2.2nF")
      (footprint "eagle-import:C0805")
      (libsource (lib "eagle-import") (part "C-USC0805"))
    )
    (comp (ref "C61")
      (value "2.2nF")
      (footprint "eagle-import:C0805")
      (libsource (lib "eagle-import") (part "C-USC0805"))
    )
    (comp (ref "C62")
      (value "2.2nF")
      (footprint "eagle-import:C0805")
      (libsource (lib "eagle-import") (part "C-USC0805"))
    )
    (comp (ref "IC25")
      (value "REF1004U")
      (footprint "eagle-import:SO08")
      (fields (field (name "MF") "TEXAS INSTRUMENTS") (field (name "MPN") "REF1004C-1.2"))
      (libsource (lib "eagle-import") (part "REF1004U"))
    )
    (comp (ref "R73")
      (value "20K")
      (footprint "eagle-import:R0805")
      (libsource (lib "eagle-import") (part "R-US_R0805"))
    )
    (comp (ref "R74")
      (value "1K")
      (footprint "eagle-import:R0805")
      (libsource (lib "eagle-import") (part "R-US_R0805"))
    )
    (comp (ref "R75")
      (value "100R")
      (footprint "eagle-import:R0805")
      (libsource (lib "eagle-import") (part "R-US_R0805"))
    )
    (comp (ref "R76")
      (value "1K")
      (footprint "eagle-import:R0805")
      (libsource (lib "eagle-import") (part "R-US_R0805"))
    )
    (comp (ref "R77")
      (value "100R")
      (footprint "eagle-import:R0805")
      (libsource (lib "eagle-import") (part "R-US_R0805"))
    )
    (comp (ref "R78")
      (value "100R")
      (footprint "eagle-import:R0805")
      (libsource (lib "eagle-import") (part "R-US_R0805"))
    )
    (comp (ref "U1")
      (value "OPA350EA/2K5")
      (footprint "eagle-import:DGK8_TEX")
      (fields
        (field (name "MANUFACTURER") "Texas Instruments")
        (field (name "COPYRIGHT") "Copyright (C) 2018 Accelerated Designs. All rights reserved")
      )
      (libsource (lib "eagle-import") (part "OPA350EA/2K5"))
    )
    (comp (ref "U2")
      (value "OPA350EA/2K5")
      (footprint "eagle-import:DGK8_TEX")
      (fields
        (field (name "MANUFACTURER") "Texas Instruments")
        (field (name "COPYRIGHT") "Copyright (C) 2018 Accelerated Designs. All rights reserved")
      )
      (libsource (lib "eagle-import") (part "OPA350EA/2K5"))
    )
    (comp (ref "C31")
      (value "10uF")
      (footprint "eagle-import:C0805")
      (libsource (lib "eagle-import") (part "C-USC0805"))
    )
    (comp (ref "C32")
      (value "10uF")
      (footprint "eagle-import:C0805")
      (libsource (lib "eagle-import") (part "C-USC0805"))
    )
    (comp (ref "C33")
      (value "0.1uF")
      (footprint "eagle-import:C0805")
      (libsource (lib "eagle-import") (part "C-USC0805"))
    )
    (comp (ref "C34")
      (value "10uF")
      (footprint "eagle-import:C0805")
      (libsource (lib "eagle-import") (part "C-USC0805"))
    )
    (comp (ref "C35")
      (value "10uF")
      (footprint "eagle-import:C0805")
      (libsource (lib "eagle-import") (part "C-USC0805"))
    )
    (comp (ref "C36")
      (value "0.1uF")
      (footprint "eagle-import:C0805")
      (libsource (lib "eagle-import") (part "C-USC0805"))
    )
    (comp (ref "IC19")
      (value "OPA1632DR")
      (footprint "eagle-import:SOIC127P600X175-8N")
      (fields (field (name "MOUSER_PART_NUMBER") "595-OPA1632DR"))
      (libsource (lib "eagle-import") (part "OPA1632DR"))
    )
    (comp (ref "IC20")
      (value "OPA1632DR")
      (footprint "eagle-import:SOIC127P600X175-8N")
      (fields (field (name "MOUSER_PART_NUMBER") "595-OPA1632DR"))
      (libsource (lib "eagle-import") (part "OPA1632DR"))
    )
    (comp (ref "R37")
      (value "1K")
      (footprint "eagle-import:R0805")
      (libsource (lib "eagle-import") (part "R-US_R0805"))
    )
    (comp (ref "R38")
      (value "249R")
      (footprint "eagle-import:R0805")
      (libsource (lib "eagle-import") (part "R-US_R0805"))
    )
    (comp (ref "R39")
      (value "49.9R")
      (footprint "eagle-import:R0805")
      (libsource (lib "eagle-import") (part "R-US_R0805"))
    )
    (comp (ref "R40")
      (value "249R")
      (footprint "eagle-import:R0805")
      (libsource (lib "eagle-import") (part "R-US_R0805"))
    )
    (comp (ref "R41")
      (value "49.9R")
      (footprint "eagle-import:R0805")
      (libsource (lib "eagle-import") (part "R-US_R0805"))
    )
    (comp (ref "R42")
      (value "1K")
      (footprint "eagle-import:R0805")
      (libsource (lib "eagle-import") (part "R-US_R0805"))
    )
    (comp (ref "R43")
      (value "1K")
      (footprint "eagle-import:R0805")
      (libsource (lib "eagle-import") (part "R-US_R0805"))
    )
    (comp (ref "R44")
      (value "249R")
      (footprint "eagle-import:R0805")
      (libsource (lib "eagle-import") (part "R-US_R0805"))
    )
    (comp (ref "R45")
      (value "49.9R")
      (footprint "eagle-import:R0805")
      (libsource (lib "eagle-import") (part "R-US_R0805"))
    )
    (comp (ref "R46")
      (value "249R")
      (footprint "eagle-import:R0805")
      (libsource (lib "eagle-import") (part "R-US_R0805"))
    )
    (comp (ref "R47")
      (value "49.9R")
      (footprint "eagle-import:R0805")
      (libsource (lib "eagle-import") (part "R-US_R0805"))
    )
    (comp (ref "R48")
      (value "1K")
      (footprint "eagle-import:R0805")
      (libsource (lib "eagle-import") (part "R-US_R0805"))
    )
    (comp (ref "C43")
      (value "10uF")
      (footprint "eagle-import:C0805")
      (libsource (lib "eagle-import") (part "C-USC0805"))
    )
    (comp (ref "C44")
      (value "10uF")
      (footprint "eagle-import:C0805")
      (libsource (lib "eagle-import") (part "C-USC0805"))
    )
    (comp (ref "C45")
      (value "0.1uF")
      (footprint "eagle-import:C0805")
      (libsource (lib "eagle-import") (part "C-USC0805"))
    )
    (comp (ref "C46")
      (value "10uF")
      (footprint "eagle-import:C0805")
      (libsource (lib "eagle-import") (part "C-USC0805"))
    )
    (comp (ref "C47")
      (value "10uF")
      (footprint "eagle-import:C0805")
      (libsource (lib "eagle-import") (part "C-USC0805"))
    )
    (comp (ref "C48")
      (value "0.1uF")
      (footprint "eagle-import:C0805")
      (libsource (lib "eagle-import") (part "C-USC0805"))
    )
    (comp (ref "IC23")
      (value "OPA1632DR")
      (footprint "eagle-import:SOIC127P600X175-8N")
      (fields (field (name "MOUSER_PART_NUMBER") "595-OPA1632DR"))
      (libsource (lib "eagle-import") (part "OPA1632DR"))
    )
    (comp (ref "IC24")
      (value "OPA1632DR")
      (footprint "eagle-import:SOIC127P600X175-8N")
      (fields (field (name "MOUSER_PART_NUMBER") "595-OPA1632DR"))
      (libsource (lib "eagle-import") (part "OPA1632DR"))
    )
    (comp (ref "R61")
      (value "1K")
      (footprint "eagle-import:R0805")
      (libsource (lib "eagle-import") (part "R-US_R0805"))
    )
    (comp (ref "R62")
      (value "249R")
      (footprint "eagle-import:R0805")
      (libsource (lib "eagle-import") (part "R-US_R0805"))
    )
    (comp (ref "R63")
      (value "49.9R")
      (footprint "eagle-import:R0805")
      (libsource (lib "eagle-import") (part "R-US_R0805"))
    )
    (comp (ref "R64")
      (value "249R")
      (footprint "eagle-import:R0805")
      (libsource (lib "eagle-import") (part "R-US_R0805"))
    )
    (comp (ref "R65")
      (value "49.9R")
      (footprint "eagle-import:R0805")
      (libsource (lib "eagle-import") (part "R-US_R0805"))
    )
    (comp (ref "R66")
      (value "1K")
      (footprint "eagle-import:R0805")
      (libsource (lib "eagle-import") (part "R-US_R0805"))
    )
    (comp (ref "R67")
      (value "1K")
      (footprint "eagle-import:R0805")
      (libsource (lib "eagle-import") (part "R-US_R0805"))
    )
    (comp (ref "R68")
      (value "249R")
      (footprint "eagle-import:R0805")
      (libsource (lib "eagle-import") (part "R-US_R0805"))
    )
    (comp (ref "R69")
      (value "49.9R")
      (footprint "eagle-import:R0805")
      (libsource (lib "eagle-import") (part "R-US_R0805"))
    )
    (comp (ref "R70")
      (value "249R")
      (footprint "eagle-import:R0805")
      (libsource (lib "eagle-import") (part "R-US_R0805"))
    )
    (comp (ref "R71")
      (value "49.9R")
      (footprint "eagle-import:R0805")
      (libsource (lib "eagle-import") (part "R-US_R0805"))
    )
    (comp (ref "R72")
      (value "1K")
      (footprint "eagle-import:R0805")
      (libsource (lib "eagle-import") (part "R-US_R0805"))
    )
    (comp (ref "JP1")
      (value "PINHD-2X10")
      (footprint "eagle-import:2X10")
      (libsource (lib "eagle-import") (part "PINHD-2X10"))
    )
    (comp (ref "JP2")
      (value "PINHD-2X10")
      (footprint "eagle-import:2X10")
      (libsource (lib "eagle-import") (part "PINHD-2X10"))
    )
    (comp (ref "C1")
      (value "20nF")
      (footprint "eagle-import:C0805")
      (libsource (lib "eagle-import") (part "C-USC0805"))
    )
    (comp (ref "C2")
      (value "18uF")
      (footprint "eagle-import:C0805")
      (libsource (lib "eagle-import") (part "C-USC0805"))
    )
    (comp (ref "C3")
      (value "39uF")
      (footprint "eagle-import:C0805")
      (libsource (lib "eagle-import") (part "C-USC0805"))
    )
    (comp (ref "C4")
      (value "20nF")
      (footprint "eagle-import:C0805")
      (libsource (lib "eagle-import") (part "C-USC0805"))
    )
    (comp (ref "C5")
      (value "18uF")
      (footprint "eagle-import:C0805")
      (libsource (lib "eagle-import") (part "C-USC0805"))
    )
    (comp (ref "C6")
      (value "39uF")
      (footprint "eagle-import:C0805")
      (libsource (lib "eagle-import") (part "C-USC0805"))
    )
    (comp (ref "IC1")
      (value "TLV2771CDBVR")
      (footprint "eagle-import:SOT95P280X145-5N")
      (fields (field (name "MOUSER_PART_NUMBER") "595-TLV2771CDBVR"))
      (libsource (lib "eagle-import") (part "TLV2771CDBVR"))
    )
    (comp (ref "IC2")
      (value "TLV2771CDBVR")
      (footprint "eagle-import:SOT95P280X145-5N")
      (fields (field (name "MOUSER_PART_NUMBER") "595-TLV2771CDBVR"))
      (libsource (lib "eagle-import") (part "TLV2771CDBVR"))
    )
    (comp (ref "IC3")
      (value "MCP601OT")
      (footprint "eagle-import:SOT23-5")
      (libsource (lib "eagle-import") (part "MCP601OT"))
    )
    (comp (ref "IC4")
      (value "MCP601OT")
      (footprint "eagle-import:SOT23-5")
      (libsource (lib "eagle-import") (part "MCP601OT"))
    )
    (comp (ref "J1")
      (value "1711026")
      (footprint "eagle-import:SHDR2W110P0X500_1X2_1000X1120X")
      (fields (field (name "MOUSER_PART_NUMBER") "651-1711026"))
      (libsource (lib "eagle-import") (part "1711026"))
    )
    (comp (ref "J2")
      (value "1711026")
      (footprint "eagle-import:SHDR2W110P0X500_1X2_1000X1120X")
      (fields (field (name "MOUSER_PART_NUMBER") "651-1711026"))
      (libsource (lib "eagle-import") (part "1711026"))
    )
    (comp (ref "R1")
      (value "200M")
      (footprint "eagle-import:R0805")
      (libsource (lib "eagle-import") (part "R-US_R0805"))
    )
    (comp (ref "R2")
      (value "13.3K")
      (footprint "eagle-import:R0805")
      (libsource (lib "eagle-import") (part "R-US_R0805"))
    )
    (comp (ref "R3")
      (value "7.5K")
      (footprint "eagle-import:R0805")
      (libsource (lib "eagle-import") (part "R-US_R0805"))
    )
    (comp (ref "R4")
      (value "200M")
      (footprint "eagle-import:R0805")
      (libsource (lib "eagle-import") (part "R-US_R0805"))
    )
    (comp (ref "R5")
      (value "13.3K")
      (footprint "eagle-import:R0805")
      (libsource (lib "eagle-import") (part "R-US_R0805"))
    )
    (comp (ref "R6")
      (value "7.5K")
      (footprint "eagle-import:R0805")
      (libsource (lib "eagle-import") (part "R-US_R0805"))
    )
    (comp (ref "C13")
      (value "20nF")
      (footprint "eagle-import:C0805")
      (libsource (lib "eagle-import") (part "C-USC0805"))
    )
    (comp (ref "C14")
      (value "18uF")
      (footprint "eagle-import:C0805")
      (libsource (lib "eagle-import") (part "C-USC0805"))
    )
    (comp (ref "C15")
      (value "39uF")
      (footprint "eagle-import:C0805")
      (libsource (lib "eagle-import") (part "C-USC0805"))
    )
    (comp (ref "C16")
      (value "20nF")
      (footprint "eagle-import:C0805")
      (libsource (lib "eagle-import") (part "C-USC0805"))
    )
    (comp (ref "C17")
      (value "18uF")
      (footprint "eagle-import:C0805")
      (libsource (lib "eagle-import") (part "C-USC0805"))
    )
    (comp (ref "C18")
      (value "39uF")
      (footprint "eagle-import:C0805")
      (libsource (lib "eagle-import") (part "C-USC0805"))
    )
    (comp (ref "IC9")
      (value "TLV2771CDBVR")
      (footprint "eagle-import:SOT95P280X145-5N")
      (fields (field (name "MOUSER_PART_NUMBER") "595-TLV2771CDBVR"))
      (libsource (lib "eagle-import") (part "TLV2771CDBVR"))
    )
    (comp (ref "IC10")
      (value "MCP601OT")
      (footprint "eagle-import:SOT23-5")
      (libsource (lib "eagle-import") (part "MCP601OT"))
    )
    (comp (ref "IC11")
      (value "TLV2771CDBVR")
      (footprint "eagle-import:SOT95P280X145-5N")
      (fields (field (name "MOUSER_PART_NUMBER") "595-TLV2771CDBVR"))
      (libsource (lib "eagle-import") (part "TLV2771CDBVR"))
    )
    (comp (ref "IC12")
      (value "MCP601OT")
      (footprint "eagle-import:SOT23-5")
      (libsource (lib "eagle-import") (part "MCP601OT"))
    )
    (comp (ref "J5")
      (value "1711026")
      (footprint "eagle-import:SHDR2W110P0X500_1X2_1000X1120X")
      (fields (field (name "MOUSER_PART_NUMBER") "651-1711026"))
      (libsource (lib "eagle-import") (part "1711026"))
    )
    (comp (ref "J6")
      (value "1711026")
      (footprint "eagle-import:SHDR2W110P0X500_1X2_1000X1120X")
      (fields (field (name "MOUSER_PART_NUMBER") "651-1711026"))
      (libsource (lib "eagle-import") (part "1711026"))
    )
    (comp (ref "R13")
      (value "200M")
      (footprint "eagle-import:R0805")
      (libsource (lib "eagle-import") (part "R-US_R0805"))
    )
    (comp (ref "R14")
      (value "13.3K")
      (footprint "eagle-import:R0805")
      (libsource (lib "eagle-import") (part "R-US_R0805"))
    )
    (comp (ref "R15")
      (value "7.5K")
      (footprint "eagle-import:R0805")
      (libsource (lib "eagle-import") (part "R-US_R0805"))
    )
    (comp (ref "R16")
      (value "200M")
      (footprint "eagle-import:R0805")
      (libsource (lib "eagle-import") (part "R-US_R0805"))
    )
    (comp (ref "R17")
      (value "13.3K")
      (footprint "eagle-import:R0805")
      (libsource (lib "eagle-import") (part "R-US_R0805"))
    )
    (comp (ref "R18")
      (value "7.5K")
      (footprint "eagle-import:R0805")
      (libsource (lib "eagle-import") (part "R-US_R0805"))
    )
  )
  (nets
    (net (code "1") (name "+1V8") (class "Default")
      (node (ref "C65") (pin "1") (pinfunction "1_1") (pintype "passive"))
      (node (ref "JP1") (pin "19") (pinfunction "19_19") (pintype "passive"))
      (node (ref "JP1") (pin "20") (pinfunction "20_20") (pintype "passive"))
      (node (ref "U3") (pin "26") (pinfunction "DVDD_26") (pintype "power_in"))
    )
    (net (code "2") (name "+3V3") (class "Default")
      (node (ref "C64") (pin "1") (pinfunction "1_1") (pintype "passive"))
      (node (ref "JP1") (pin "17") (pinfunction "17_17") (pintype "passive"))
      (node (ref "JP1") (pin "18") (pinfunction "18_18") (pintype "passive"))
      (node (ref "SJ1") (pin "1") (pinfunction "1_1") (pintype "passive"))
      (node (ref "U3") (pin "10") (pinfunction "CLKDIV_10") (pintype "input"))
      (node (ref "U3") (pin "22") (pinfunction "IOVDD_2_22") (pintype "power_in"))
      (node (ref "U3") (pin "23") (pinfunction "IOVDD_23") (pintype "power_in"))
      (node (ref "U3") (pin "31") (pinfunction "FORMAT1_31") (pintype "input"))
    )
    (net (code "3") (name "+5V") (class "Default")
      (node (ref "C63") (pin "1") (pinfunction "1_1") (pintype "passive"))
      (node (ref "IC1") (pin "5") (pinfunction "VDD_5") (pintype "bidirectional"))
      (node (ref "IC10") (pin "5") (pinfunction "V+_5") (pintype "power_in"))
      (node (ref "IC11") (pin "5") (pinfunction "VDD_5") (pintype "bidirectional"))
      (node (ref "IC12") (pin "5") (pinfunction "V+_5") (pintype "power_in"))
      (node (ref "IC13") (pin "5") (pinfunction "VDD_5") (pintype "bidirectional"))
      (node (ref "IC14") (pin "5") (pinfunction "V+_5") (pintype "power_in"))
      (node (ref "IC15") (pin "5") (pinfunction "VDD_5") (pintype "bidirectional"))
      (node (ref "IC16") (pin "5") (pinfunction "V+_5") (pintype "power_in"))
      (node (ref "IC2") (pin "5") (pinfunction "VDD_5") (pintype "bidirectional"))
      (node (ref "IC3") (pin "5") (pinfunction "V+_5") (pintype "power_in"))
      (node (ref "IC4") (pin "5") (pinfunction "V+_5") (pintype "power_in"))
      (node (ref "IC5") (pin "5") (pinfunction "VDD_5") (pintype "bidirectional"))
      (node (ref "IC6") (pin "5") (pinfunction "V+_5") (pintype "power_in"))
      (node (ref "IC7") (pin "5") (pinfunction "VDD_5") (pintype "bidirectional"))
      (node (ref "IC8") (pin "5") (pinfunction "V+_5") (pintype "power_in"))
      (node (ref "IC9") (pin "5") (pinfunction "VDD_5") (pintype "bidirectional"))
      (node (ref "JP1") (pin "13") (pinfunction "13_13") (pintype "passive"))
      (node (ref "JP1") (pin "14") (pinfunction "14_14") (pintype "passive"))
      (node (ref "R73") (pin "2") (pinfunction "2_2") (pintype "passive"))
      (node (ref "U1") (pin "7") (pinfunction "V+_7") (pintype "power_in"))
      (node (ref "U2") (pin "7") (pinfunction "V+_7") (pintype "power_in"))
      (node (ref "U3") (pin "44") (pinfunction "AVDD_3_44") (pintype "power_in"))
      (node (ref "U3") (pin "5") (pinfunction "AVDD_2_5") (pintype "power_in"))
      (node (ref "U3") (pin "60") (pinfunction "AVDD_60") (pintype "power_in"))
    )
    (net (code "4") (name "+12V") (class "Default")
      (node (ref "IC17") (pin "3") (pinfunction "V+_3") (pintype "bidirectional"))
      (node (ref "IC18") (pin "3") (pinfunction "V+_3") (pintype "bidirectional"))
      (node (ref "IC19") (pin "3") (pinfunction "V+_3") (pintype "bidirectional"))
      (node (ref "IC20") (pin "3") (pinfunction "V+_3") (pintype "bidirectional"))
      (node (ref "IC21") (pin "3") (pinfunction "V+_3") (pintype "bidirectional"))
      (node (ref "IC22") (pin "3") (pinfunction "V+_3") (pintype "bidirectional"))
      (node (ref "IC23") (pin "3") (pinfunction "V+_3") (pintype "bidirectional"))
      (node (ref "IC24") (pin "3") (pinfunction "V+_3") (pintype "bidirectional"))
      (node (ref "JP1") (pin "1") (pinfunction "1_1") (pintype "passive"))
      (node (ref "JP1") (pin "2") (pinfunction "2_2") (pintype "passive"))
    )
    (net (code "5") (name "+24V") (class "Default")
      (node (ref "JP1") (pin "10") (pinfunction "10_10") (pintype "passive"))
      (node (ref "JP1") (pin "9") (pinfunction "9_9") (pintype "passive"))
    )
    (net (code "6") (name "-12V") (class "Default")
      (node (ref "IC17") (pin "6") (pinfunction "V-_6") (pintype "bidirectional"))
      (node (ref "IC18") (pin "6") (pinfunction "V-_6") (pintype "bidirectional"))
      (node (ref "IC19") (pin "6") (pinfunction "V-_6") (pintype "bidirectional"))
      (node (ref "IC20") (pin "6") (pinfunction "V-_6") (pintype "bidirectional"))
      (node (ref "IC21") (pin "6") (pinfunction "V-_6") (pintype "bidirectional"))
      (node (ref "IC22") (pin "6") (pinfunction "V-_6") (pintype "bidirectional"))
      (node (ref "IC23") (pin "6") (pinfunction "V-_6") (pintype "bidirectional"))
      (node (ref "IC24") (pin "6") (pinfunction "V-_6") (pintype "bidirectional"))
      (node (ref "JP1") (pin "5") (pinfunction "5_5") (pintype "passive"))
      (node (ref "JP1") (pin "6") (pinfunction "6_6") (pintype "passive"))
    )
    (net (code "7") (name "AINN1") (class "Default")
      (node (ref "C55") (pin "2") (pinfunction "2_2") (pintype "passive"))
      (node (ref "R34") (pin "1") (pinfunction "1_1") (pintype "passive"))
      (node (ref "R35") (pin "1") (pinfunction "1_1") (pintype "passive"))
      (node (ref "U3") (pin "4") (pinfunction "AINN1_4") (pintype "input"))
    )
    (net (code "8") (name "AINN2") (class "Default")
      (node (ref "C56") (pin "2") (pinfunction "2_2") (pintype "passive"))
      (node (ref "R52") (pin "1") (pinfunction "1_1") (pintype "passive"))
      (node (ref "R53") (pin "1") (pinfunction "1_1") (pintype "passive"))
      (node (ref "U3") (pin "2") (pinfunction "AINN2_2") (pintype "input"))
    )
    (net (code "9") (name "AINN3") (class "Default")
      (node (ref "C57") (pin "2") (pinfunction "2_2") (pintype "passive"))
      (node (ref "R40") (pin "1") (pinfunction "1_1") (pintype "passive"))
      (node (ref "R41") (pin "1") (pinfunction "1_1") (pintype "passive"))
      (node (ref "U3") (pin "64") (pinfunction "AINN3_64") (pintype "input"))
    )
    (net (code "10") (name "AINN4") (class "Default")
      (node (ref "C58") (pin "2") (pinfunction "2_2") (pintype "passive"))
      (node (ref "R46") (pin "1") (pinfunction "1_1") (pintype "passive"))
      (node (ref "R47") (pin "1") (pinfunction "1_1") (pintype "passive"))
      (node (ref "U3") (pin "62") (pinfunction "AINN4_62") (pintype "input"))
    )
    (net (code "11") (name "AINN5") (class "Default")
      (node (ref "C59") (pin "2") (pinfunction "2_2") (pintype "passive"))
      (node (ref "R28") (pin "1") (pinfunction "1_1") (pintype "passive"))
      (node (ref "R29") (pin "1") (pinfunction "1_1") (pintype "passive"))
      (node (ref "U3") (pin "52") (pinfunction "AINN5_52") (pintype "input"))
    )
    (net (code "12") (name "AINN6") (class "Default")
      (node (ref "C60") (pin "2") (pinfunction "2_2") (pintype "passive"))
      (node (ref "R70") (pin "1") (pinfunction "1_1") (pintype "passive"))
      (node (ref "R71") (pin "1") (pinfunction "1_1") (pintype "passive"))
      (node (ref "U3") (pin "50") (pinfunction "AINN6_50") (pintype "input"))
    )
    (net (code "13") (name "AINN7") (class "Default")
      (node (ref "C61") (pin "2") (pinfunction "2_2") (pintype "passive"))
      (node (ref "R64") (pin "1") (pinfunction "1_1") (pintype "passive"))
      (node (ref "R65") (pin "1") (pinfunction "1_1") (pintype "passive"))
      (node (ref "U3") (pin "48") (pinfunction "AINN7_48") (pintype "input"))
    )
    (net (code "14") (name "AINN8") (class "Default")
      (node (ref "C62") (pin "2") (pinfunction "2_2") (pintype "passive"))
      (node (ref "R58") (pin "1") (pinfunction "1_1") (pintype "passive"))
      (node (ref "R59") (pin "1") (pinfunction "1_1") (pintype "passive"))
      (node (ref "U3") (pin "46") (pinfunction "AINN8_46") (pintype "input"))
    )
    (net (code "15") (name "AINP1") (class "Default")
      (node (ref "C55") (pin "1") (pinfunction "1_1") (pintype "passive"))
      (node (ref "R32") (pin "2") (pinfunction "2_2") (pintype "passive"))
      (node (ref "R33") (pin "2") (pinfunction "2_2") (pintype "passive"))
      (node (ref "U3") (pin "3") (pinfunction "AINP1_3") (pintype "input"))
    )
    (net (code "16") (name "AINP2") (class "Default")
      (node (ref "C56") (pin "1") (pinfunction "1_1") (pintype "passive"))
      (node (ref "R50") (pin "2") (pinfunction "2_2") (pintype "passive"))
      (node (ref "R51") (pin "2") (pinfunction "2_2") (pintype "passive"))
      (node (ref "U3") (pin "1") (pinfunction "AINP2_1") (pintype "input"))
    )
    (net (code "17") (name "AINP3") (class "Default")
      (node (ref "C57") (pin "1") (pinfunction "1_1") (pintype "passive"))
      (node (ref "R38") (pin "2") (pinfunction "2_2") (pintype "passive"))
      (node (ref "R39") (pin "2") (pinfunction "2_2") (pintype "passive"))
      (node (ref "U3") (pin "63") (pinfunction "AINP3_63") (pintype "input"))
    )
    (net (code "18") (name "AINP4") (class "Default")
      (node (ref "C58") (pin "1") (pinfunction "1_1") (pintype "passive"))
      (node (ref "R44") (pin "2") (pinfunction "2_2") (pintype "passive"))
      (node (ref "R45") (pin "2") (pinfunction "2_2") (pintype "passive"))
      (node (ref "U3") (pin "61") (pinfunction "AINP4_61") (pintype "input"))
    )
    (net (code "19") (name "AINP5") (class "Default")
      (node (ref "C59") (pin "1") (pinfunction "1_1") (pintype "passive"))
      (node (ref "R26") (pin "2") (pinfunction "2_2") (pintype "passive"))
      (node (ref "R27") (pin "2") (pinfunction "2_2") (pintype "passive"))
      (node (ref "U3") (pin "51") (pinfunction "AINP5_51") (pintype "input"))
    )
    (net (code "20") (name "AINP6") (class "Default")
      (node (ref "C60") (pin "1") (pinfunction "1_1") (pintype "passive"))
      (node (ref "R68") (pin "2") (pinfunction "2_2") (pintype "passive"))
      (node (ref "R69") (pin "2") (pinfunction "2_2") (pintype "passive"))
      (node (ref "U3") (pin "49") (pinfunction "AINP6_49") (pintype "input"))
    )
    (net (code "21") (name "AINP7") (class "Default")
      (node (ref "C61") (pin "1") (pinfunction "1_1") (pintype "passive"))
      (node (ref "R62") (pin "2") (pinfunction "2_2") (pintype "passive"))
      (node (ref "R63") (pin "2") (pinfunction "2_2") (pintype "passive"))
      (node (ref "U3") (pin "47") (pinfunction "AINP7_47") (pintype "input"))
    )
    (net (code "22") (name "AINP8") (class "Default")
      (node (ref "C62") (pin "1") (pinfunction "1_1") (pintype "passive"))
      (node (ref "R56") (pin "2") (pinfunction "2_2") (pintype "passive"))
      (node (ref "R57") (pin "2") (pinfunction "2_2") (pintype "passive"))
      (node (ref "U3") (pin "45") (pinfunction "AINP8_45") (pintype "input"))
    )
    (net (code "23") (name "CLK") (class "Default")
      (node (ref "JP2") (pin "9") (pinfunction "9_9") (pintype "passive"))
      (node (ref "U3") (pin "27") (pinfunction "CLK_27") (pintype "input"))
    )
    (net (code "24") (name "DOUT1") (class "Default")
      (node (ref "JP2") (pin "10") (pinfunction "10_10") (pintype "passive"))
      (node (ref "U3") (pin "20") (pinfunction "DOUT1_20") (pintype "output"))
    )
    (net (code "25") (name "DOUT2") (class "Default")
      (node (ref "JP2") (pin "7") (pinfunction "7_7") (pintype "passive"))
      (node (ref "U3") (pin "19") (pinfunction "DOUT2_19") (pintype "output"))
    )
    (net (code "26") (name "DOUT3") (class "Default")
      (node (ref "JP2") (pin "8") (pinfunction "8_8") (pintype "passive"))
      (node (ref "U3") (pin "18") (pinfunction "DOUT3_18") (pintype "output"))
    )
    (net (code "27") (name "DOUT4") (class "Default")
      (node (ref "JP2") (pin "5") (pinfunction "5_5") (pintype "passive"))
      (node (ref "U3") (pin "17") (pinfunction "DOUT4_17") (pintype "output"))
    )
    (net (code "28") (name "DOUT5") (class "Default")
      (node (ref "JP2") (pin "6") (pinfunction "6_6") (pintype "passive"))
      (node (ref "U3") (pin "16") (pinfunction "DOUT5_16") (pintype "output"))
    )
    (net (code "29") (name "DOUT6") (class "Default")
      (node (ref "JP2") (pin "3") (pinfunction "3_3") (pintype "passive"))
      (node (ref "U3") (pin "15") (pinfunction "DOUT6_15") (pintype "output"))
    )
    (net (code "30") (name "DOUT7") (class "Default")
      (node (ref "JP2") (pin "4") (pinfunction "4_4") (pintype "passive"))
      (node (ref "U3") (pin "14") (pinfunction "DOUT7_14") (pintype "output"))
    )
    (net (code "31") (name "DOUT8") (class "Default")
      (node (ref "JP2") (pin "1") (pinfunction "1_1") (pintype "passive"))
      (node (ref "U3") (pin "13") (pinfunction "DOUT8_13") (pintype "output"))
    )
    (net (code "32") (name "DRDY") (class "Default")
      (node (ref "JP2") (pin "11") (pinfunction "11_11") (pintype "passive"))
      (node (ref "U3") (pin "29") (pinfunction "~{DRDY/FSYNC}_29") (pintype "bidirectional"))
    )
    (net (code "33") (name "GND") (class "Default")
      (node (ref "C11") (pin "2") (pinfunction "2_2") (pintype "passive"))
      (node (ref "C14") (pin "2") (pinfunction "2_2") (pintype "passive"))
      (node (ref "C17") (pin "2") (pinfunction "2_2") (pintype "passive"))
      (node (ref "C2") (pin "2") (pinfunction "2_2") (pintype "passive"))
      (node (ref "C20") (pin "2") (pinfunction "2_2") (pintype "passive"))
      (node (ref "C23") (pin "2") (pinfunction "2_2") (pintype "passive"))
      (node (ref "C27") (pin "2") (pinfunction "2_2") (pintype "passive"))
      (node (ref "C30") (pin "2") (pinfunction "2_2") (pintype "passive"))
      (node (ref "C33") (pin "2") (pinfunction "2_2") (pintype "passive"))
      (node (ref "C36") (pin "2") (pinfunction "2_2") (pintype "passive"))
      (node (ref "C39") (pin "2") (pinfunction "2_2") (pintype "passive"))
      (node (ref "C42") (pin "2") (pinfunction "2_2") (pintype "passive"))
      (node (ref "C45") (pin "2") (pinfunction "2_2") (pintype "passive"))
      (node (ref "C48") (pin "2") (pinfunction "2_2") (pintype "passive"))
      (node (ref "C49") (pin "2") (pinfunction "2_2") (pintype "passive"))
      (node (ref "C5") (pin "2") (pinfunction "2_2") (pintype "passive"))
      (node (ref "C50") (pin "2") (pinfunction "2_2") (pintype "passive"))
      (node (ref "C52") (pin "2") (pinfunction "2_2") (pintype "passive"))
      (node (ref "C53") (pin "2") (pinfunction "2_2") (pintype "passive"))
      (node (ref "C54") (pin "2") (pinfunction "2_2") (pintype "passive"))
      (node (ref "C63") (pin "2") (pinfunction "2_2") (pintype "passive"))
      (node (ref "C64") (pin "2") (pinfunction "2_2") (pintype "passive"))
      (node (ref "C65") (pin "2") (pinfunction "2_2") (pintype "passive"))
      (node (ref "C8") (pin "2") (pinfunction "2_2") (pintype "passive"))
      (node (ref "IC1") (pin "2") (pinfunction "GND_2") (pintype "bidirectional"))
      (node (ref "IC1") (pin "3") (pinfunction "IN+_3") (pintype "bidirectional"))
      (node (ref "IC10") (pin "2") (pinfunction "V-_2") (pintype "power_in"))
      (node (ref "IC11") (pin "2") (pinfunction "GND_2") (pintype "bidirectional"))
      (node (ref "IC11") (pin "3") (pinfunction "IN+_3") (pintype "bidirectional"))
      (node (ref "IC12") (pin "2") (pinfunction "V-_2") (pintype "power_in"))
      (node (ref "IC13") (pin "2") (pinfunction "GND_2") (pintype "bidirectional"))
      (node (ref "IC13") (pin "3") (pinfunction "IN+_3") (pintype "bidirectional"))
      (node (ref "IC14") (pin "2") (pinfunction "V-_2") (pintype "power_in"))
      (node (ref "IC15") (pin "2") (pinfunction "GND_2") (pintype "bidirectional"))
      (node (ref "IC15") (pin "3") (pinfunction "IN+_3") (pintype "bidirectional"))
      (node (ref "IC16") (pin "2") (pinfunction "V-_2") (pintype "power_in"))
      (node (ref "IC2") (pin "2") (pinfunction "GND_2") (pintype "bidirectional"))
      (node (ref "IC2") (pin "3") (pinfunction "IN+_3") (pintype "bidirectional"))
      (node (ref "IC25") (pin "4") (pinfunction "A_4") (pintype "passive"))
      (node (ref "IC3") (pin "2") (pinfunction "V-_2") (pintype "power_in"))
      (node (ref "IC4") (pin "2") (pinfunction "V-_2") (pintype "power_in"))
      (node (ref "IC5") (pin "2") (pinfunction "GND_2") (pintype "bidirectional"))
      (node (ref "IC5") (pin "3") (pinfunction "IN+_3") (pintype "bidirectional"))
      (node (ref "IC6") (pin "2") (pinfunction "V-_2") (pintype "power_in"))
      (node (ref "IC7") (pin "2") (pinfunction "GND_2") (pintype "bidirectional"))
      (node (ref "IC7") (pin "3") (pinfunction "IN+_3") (pintype "bidirectional"))
      (node (ref "IC8") (pin "2") (pinfunction "V-_2") (pintype "power_in"))
      (node (ref "IC9") (pin "2") (pinfunction "GND_2") (pintype "bidirectional"))
      (node (ref "IC9") (pin "3") (pinfunction "IN+_3") (pintype "bidirectional"))
      (node (ref "J1") (pin "2") (pinfunction "2_2") (pintype "bidirectional"))
      (node (ref "J2") (pin "2") (pinfunction "2_2") (pintype "bidirectional"))
      (node (ref "J3") (pin "2") (pinfunction "2_2") (pintype "bidirectional"))
      (node (ref "J4") (pin "2") (pinfunction "2_2") (pintype "bidirectional"))
      (node (ref "J5") (pin "2") (pinfunction "2_2") (pintype "bidirectional"))
      (node (ref "J6") (pin "2") (pinfunction "2_2") (pintype "bidirectional"))
      (node (ref "J7") (pin "2") (pinfunction "2_2") (pintype "bidirectional"))
      (node (ref "J8") (pin "2") (pinfunction "2_2") (pintype "bidirectional"))
      (node (ref "JP1") (pin "11") (pinfunction "11_11") (pintype "passive"))
      (node (ref "JP1") (pin "12") (pinfunction "12_12") (pintype "passive"))
      (node (ref "JP1") (pin "15") (pinfunction "15_15") (pintype "passive"))
      (node (ref "JP1") (pin "16") (pinfunction "16_16") (pintype "passive"))
      (node (ref "JP1") (pin "3") (pinfunction "3_3") (pintype "passive"))
      (node (ref "JP1") (pin "4") (pinfunction "4_4") (pintype "passive"))
      (node (ref "JP1") (pin "7") (pinfunction "7_7") (pintype "passive"))
      (node (ref "JP1") (pin "8") (pinfunction "8_8") (pintype "passive"))
      (node (ref "JP2") (pin "13") (pinfunction "13_13") (pintype "passive"))
      (node (ref "JP2") (pin "14") (pinfunction "14_14") (pintype "passive"))
      (node (ref "JP2") (pin "15") (pinfunction "15_15") (pintype "passive"))
      (node (ref "JP2") (pin "16") (pinfunction "16_16") (pintype "passive"))
      (node (ref "JP2") (pin "17") (pinfunction "17_17") (pintype "passive"))
      (node (ref "JP2") (pin "18") (pinfunction "18_18") (pintype "passive"))
      (node (ref "JP2") (pin "19") (pinfunction "19_19") (pintype "passive"))
      (node (ref "JP2") (pin "20") (pinfunction "20_20") (pintype "passive"))
      (node (ref "R30") (pin "2") (pinfunction "2_2") (pintype "passive"))
      (node (ref "R36") (pin "2") (pinfunction "2_2") (pintype "passive"))
      (node (ref "R42") (pin "2") (pinfunction "2_2") (pintype "passive"))
      (node (ref "R48") (pin "2") (pinfunction "2_2") (pintype "passive"))
      (node (ref "R54") (pin "2") (pinfunction "2_2") (pintype "passive"))
      (node (ref "R60") (pin "2") (pinfunction "2_2") (pintype "passive"))
      (node (ref "R66") (pin "2") (pinfunction "2_2") (pintype "passive"))
      (node (ref "R72") (pin "2") (pinfunction "2_2") (pintype "passive"))
      (node (ref "SJ1") (pin "3") (pinfunction "3_3") (pintype "passive"))
      (node (ref "U1") (pin "4") (pinfunction "V-_4") (pintype "power_in"))
      (node (ref "U2") (pin "4") (pinfunction "V-_4") (pintype "power_in"))
      (node (ref "U3") (pin "12") (pinfunction "DIN_12") (pintype "input"))
      (node (ref "U3") (pin "21") (pinfunction "DGND_3_21") (pintype "power_in"))
      (node (ref "U3") (pin "24") (pinfunction "DGND_4_24") (pintype "power_in"))
      (node (ref "U3") (pin "25") (pinfunction "DGND_25") (pintype "power_in"))
      (node (ref "U3") (pin "30") (pinfunction "FORMAT2_30") (pintype "input"))
      (node (ref "U3") (pin "32") (pinfunction "FORMAT0_32") (pintype "input"))
      (node (ref "U3") (pin "34") (pinfunction "MODE_34") (pintype "input"))
      (node (ref "U3") (pin "43") (pinfunction "AGND_3_43") (pintype "power_in"))
      (node (ref "U3") (pin "53") (pinfunction "AVDD_4_53") (pintype "power_in"))
      (node (ref "U3") (pin "54") (pinfunction "AGND_4_54") (pintype "power_in"))
      (node (ref "U3") (pin "57") (pinfunction "VREFN_57") (pintype "power_in"))
      (node (ref "U3") (pin "58") (pinfunction "AGND_5_58") (pintype "power_in"))
      (node (ref "U3") (pin "59") (pinfunction "AGND_59") (pintype "power_in"))
      (node (ref "U3") (pin "6") (pinfunction "AGND_2_6") (pintype "power_in"))
      (node (ref "U3") (pin "7") (pinfunction "DGND_2_7") (pintype "power_in"))
      (node (ref "U3") (pin "8") (pinfunction "TEST0_8") (pintype "input"))
      (node (ref "U3") (pin "9") (pinfunction "TEST1_9") (pintype "input"))
      (node (ref "U3") (pin "EPAD") (pinfunction "EPAD_EPAD") (pintype "passive"))
    )
    (net (code "34") (name "Net-(C3-Pad1)") (class "Default")
      (node (ref "C3") (pin "1") (pinfunction "1_1") (pintype "passive"))
      (node (ref "R2") (pin "1") (pinfunction "1_1") (pintype "passive"))
      (node (ref "R3") (pin "2") (pinfunction "2_2") (pintype "passive"))
    )
    (net (code "35") (name "Net-(C6-Pad1)") (class "Default")
      (node (ref "C6") (pin "1") (pinfunction "1_1") (pintype "passive"))
      (node (ref "R5") (pin "1") (pinfunction "1_1") (pintype "passive"))
      (node (ref "R6") (pin "2") (pinfunction "2_2") (pintype "passive"))
    )
    (net (code "36") (name "Net-(C9-Pad1)") (class "Default")
      (node (ref "C9") (pin "1") (pinfunction "1_1") (pintype "passive"))
      (node (ref "R8") (pin "1") (pinfunction "1_1") (pintype "passive"))
      (node (ref "R9") (pin "2") (pinfunction "2_2") (pintype "passive"))
    )
    (net (code "37") (name "Net-(C12-Pad1)") (class "Default")
      (node (ref "C12") (pin "1") (pinfunction "1_1") (pintype "passive"))
      (node (ref "R11") (pin "1") (pinfunction "1_1") (pintype "passive"))
      (node (ref "R12") (pin "2") (pinfunction "2_2") (pintype "passive"))
    )
    (net (code "38") (name "Net-(C15-Pad1)") (class "Default")
      (node (ref "C15") (pin "1") (pinfunction "1_1") (pintype "passive"))
      (node (ref "R14") (pin "1") (pinfunction "1_1") (pintype "passive"))
      (node (ref "R15") (pin "2") (pinfunction "2_2") (pintype "passive"))
    )
    (net (code "39") (name "Net-(C18-Pad1)") (class "Default")
      (node (ref "C18") (pin "1") (pinfunction "1_1") (pintype "passive"))
      (node (ref "R17") (pin "1") (pinfunction "1_1") (pintype "passive"))
      (node (ref "R18") (pin "2") (pinfunction "2_2") (pintype "passive"))
    )
    (net (code "40") (name "Net-(C21-Pad1)") (class "Default")
      (node (ref "C21") (pin "1") (pinfunction "1_1") (pintype "passive"))
      (node (ref "R20") (pin "1") (pinfunction "1_1") (pintype "passive"))
      (node (ref "R21") (pin "2") (pinfunction "2_2") (pintype "passive"))
    )
    (net (code "41") (name "Net-(C24-Pad1)") (class "Default")
      (node (ref "C24") (pin "1") (pinfunction "1_1") (pintype "passive"))
      (node (ref "R23") (pin "1") (pinfunction "1_1") (pintype "passive"))
      (node (ref "R24") (pin "2") (pinfunction "2_2") (pintype "passive"))
    )
    (net (code "42") (name "Net-(C49-Pad1)") (class "Default")
      (node (ref "C49") (pin "1") (pinfunction "1_1") (pintype "passive"))
      (node (ref "C50") (pin "1") (pinfunction "1_1") (pintype "passive"))
      (node (ref "R74") (pin "2") (pinfunction "2_2") (pintype "passive"))
      (node (ref "R75") (pin "1") (pinfunction "1_1") (pintype "passive"))
    )
    (net (code "43") (name "Net-(IC1-IN-)") (class "Default")
      (node (ref "C1") (pin "1") (pinfunction "1_1") (pintype "passive"))
      (node (ref "IC1") (pin "4") (pinfunction "IN-_4") (pintype "bidirectional"))
      (node (ref "J1") (pin "1") (pinfunction "1_1") (pintype "bidirectional"))
      (node (ref "R1") (pin "1") (pinfunction "1_1") (pintype "passive"))
    )
    (net (code "44") (name "Net-(IC1-OUT)") (class "Default")
      (node (ref "C1") (pin "2") (pinfunction "2_2") (pintype "passive"))
      (node (ref "IC1") (pin "1") (pinfunction "OUT_1") (pintype "bidirectional"))
      (node (ref "R1") (pin "2") (pinfunction "2_2") (pintype "passive"))
      (node (ref "R3") (pin "1") (pinfunction "1_1") (pintype "passive"))
    )
    (net (code "45") (name "Net-(IC2-IN-)") (class "Default")
      (node (ref "C4") (pin "1") (pinfunction "1_1") (pintype "passive"))
      (node (ref "IC2") (pin "4") (pinfunction "IN-_4") (pintype "bidirectional"))
      (node (ref "J2") (pin "1") (pinfunction "1_1") (pintype "bidirectional"))
      (node (ref "R4") (pin "1") (pinfunction "1_1") (pintype "passive"))
    )
    (net (code "46") (name "Net-(IC2-OUT)") (class "Default")
      (node (ref "C4") (pin "2") (pinfunction "2_2") (pintype "passive"))
      (node (ref "IC2") (pin "1") (pinfunction "OUT_1") (pintype "bidirectional"))
      (node (ref "R4") (pin "2") (pinfunction "2_2") (pintype "passive"))
      (node (ref "R6") (pin "1") (pinfunction "1_1") (pintype "passive"))
    )
    (net (code "47") (name "Net-(IC3-+IN)") (class "Default")
      (node (ref "C2") (pin "1") (pinfunction "1_1") (pintype "passive"))
      (node (ref "IC3") (pin "3") (pinfunction "+IN_3") (pintype "input"))
      (node (ref "R2") (pin "2") (pinfunction "2_2") (pintype "passive"))
    )
    (net (code "48") (name "Net-(IC4-+IN)") (class "Default")
      (node (ref "C5") (pin "1") (pinfunction "1_1") (pintype "passive"))
      (node (ref "IC4") (pin "3") (pinfunction "+IN_3") (pintype "input"))
      (node (ref "R5") (pin "2") (pinfunction "2_2") (pintype "passive"))
    )
    (net (code "49") (name "Net-(IC5-IN-)") (class "Default")
      (node (ref "C7") (pin "1") (pinfunction "1_1") (pintype "passive"))
      (node (ref "IC5") (pin "4") (pinfunction "IN-_4") (pintype "bidirectional"))
      (node (ref "J3") (pin "1") (pinfunction "1_1") (pintype "bidirectional"))
      (node (ref "R7") (pin "1") (pinfunction "1_1") (pintype "passive"))
    )
    (net (code "50") (name "Net-(IC5-OUT)") (class "Default")
      (node (ref "C7") (pin "2") (pinfunction "2_2") (pintype "passive"))
      (node (ref "IC5") (pin "1") (pinfunction "OUT_1") (pintype "bidirectional"))
      (node (ref "R7") (pin "2") (pinfunction "2_2") (pintype "passive"))
      (node (ref "R9") (pin "1") (pinfunction "1_1") (pintype "passive"))
    )
    (net (code "51") (name "Net-(IC6-+IN)") (class "Default")
      (node (ref "C8") (pin "1") (pinfunction "1_1") (pintype "passive"))
      (node (ref "IC6") (pin "3") (pinfunction "+IN_3") (pintype "input"))
      (node (ref "R8") (pin "2") (pinfunction "2_2") (pintype "passive"))
    )
    (net (code "52") (name "Net-(IC7-IN-)") (class "Default")
      (node (ref "C10") (pin "1") (pinfunction "1_1") (pintype "passive"))
      (node (ref "IC7") (pin "4") (pinfunction "IN-_4") (pintype "bidirectional"))
      (node (ref "J4") (pin "1") (pinfunction "1_1") (pintype "bidirectional"))
      (node (ref "R10") (pin "1") (pinfunction "1_1") (pintype "passive"))
    )
    (net (code "53") (name "Net-(IC7-OUT)") (class "Default")
      (node (ref "C10") (pin "2") (pinfunction "2_2") (pintype "passive"))
      (node (ref "IC7") (pin "1") (pinfunction "OUT_1") (pintype "bidirectional"))
      (node (ref "R10") (pin "2") (pinfunction "2_2") (pintype "passive"))
      (node (ref "R12") (pin "1") (pinfunction "1_1") (pintype "passive"))
    )
    (net (code "54") (name "Net-(IC8-+IN)") (class "Default")
      (node (ref "C11") (pin "1") (pinfunction "1_1") (pintype "passive"))
      (node (ref "IC8") (pin "3") (pinfunction "+IN_3") (pintype "input"))
      (node (ref "R11") (pin "2") (pinfunction "2_2") (pintype "passive"))
    )
    (net (code "55") (name "Net-(IC9-IN-)") (class "Default")
      (node (ref "C13") (pin "1") (pinfunction "1_1") (pintype "passive"))
      (node (ref "IC9") (pin "4") (pinfunction "IN-_4") (pintype "bidirectional"))
      (node (ref "J5") (pin "1") (pinfunction "1_1") (pintype "bidirectional"))
      (node (ref "R13") (pin "1") (pinfunction "1_1") (pintype "passive"))
    )
    (net (code "56") (name "Net-(IC9-OUT)") (class "Default")
      (node (ref "C13") (pin "2") (pinfunction "2_2") (pintype "passive"))
      (node (ref "IC9") (pin "1") (pinfunction "OUT_1") (pintype "bidirectional"))
      (node (ref "R13") (pin "2") (pinfunction "2_2") (pintype "passive"))
      (node (ref "R15") (pin "1") (pinfunction "1_1") (pintype "passive"))
    )
    (net (code "57") (name "Net-(IC10-+IN)") (class "Default")
      (node (ref "C14") (pin "1") (pinfunction "1_1") (pintype "passive"))
      (node (ref "IC10") (pin "3") (pinfunction "+IN_3") (pintype "input"))
      (node (ref "R14") (pin "2") (pinfunction "2_2") (pintype "passive"))
    )
    (net (code "58") (name "Net-(IC11-IN-)") (class "Default")
      (node (ref "C16") (pin "1") (pinfunction "1_1") (pintype "passive"))
      (node (ref "IC11") (pin "4") (pinfunction "IN-_4") (pintype "bidirectional"))
      (node (ref "J6") (pin "1") (pinfunction "1_1") (pintype "bidirectional"))
      (node (ref "R16") (pin "1") (pinfunction "1_1") (pintype "passive"))
    )
    (net (code "59") (name "Net-(IC11-OUT)") (class "Default")
      (node (ref "C16") (pin "2") (pinfunction "2_2") (pintype "passive"))
      (node (ref "IC11") (pin "1") (pinfunction "OUT_1") (pintype "bidirectional"))
      (node (ref "R16") (pin "2") (pinfunction "2_2") (pintype "passive"))
      (node (ref "R18") (pin "1") (pinfunction "1_1") (pintype "passive"))
    )
    (net (code "60") (name "Net-(IC12-+IN)") (class "Default")
      (node (ref "C17") (pin "1") (pinfunction "1_1") (pintype "passive"))
      (node (ref "IC12") (pin "3") (pinfunction "+IN_3") (pintype "input"))
      (node (ref "R17") (pin "2") (pinfunction "2_2") (pintype "passive"))
    )
    (net (code "61") (name "Net-(IC13-IN-)") (class "Default")
      (node (ref "C19") (pin "1") (pinfunction "1_1") (pintype "passive"))
      (node (ref "IC13") (pin "4") (pinfunction "IN-_4") (pintype "bidirectional"))
      (node (ref "J7") (pin "1") (pinfunction "1_1") (pintype "bidirectional"))
      (node (ref "R19") (pin "1") (pinfunction "1_1") (pintype "passive"))
    )
    (net (code "62") (name "Net-(IC13-OUT)") (class "Default")
      (node (ref "C19") (pin "2") (pinfunction "2_2") (pintype "passive"))
      (node (ref "IC13") (pin "1") (pinfunction "OUT_1") (pintype "bidirectional"))
      (node (ref "R19") (pin "2") (pinfunction "2_2") (pintype "passive"))
      (node (ref "R21") (pin "1") (pinfunction "1_1") (pintype "passive"))
    )
    (net (code "63") (name "Net-(IC14-+IN)") (class "Default")
      (node (ref "C20") (pin "1") (pinfunction "1_1") (pintype "passive"))
      (node (ref "IC14") (pin "3") (pinfunction "+IN_3") (pintype "input"))
      (node (ref "R20") (pin "2") (pinfunction "2_2") (pintype "passive"))
    )
    (net (code "64") (name "Net-(IC15-IN-)") (class "Default")
      (node (ref "C22") (pin "1") (pinfunction "1_1") (pintype "passive"))
      (node (ref "IC15") (pin "4") (pinfunction "IN-_4") (pintype "bidirectional"))
      (node (ref "J8") (pin "1") (pinfunction "1_1") (pintype "bidirectional"))
      (node (ref "R22") (pin "1") (pinfunction "1_1") (pintype "passive"))
    )
    (net (code "65") (name "Net-(IC15-OUT)") (class "Default")
      (node (ref "C22") (pin "2") (pinfunction "2_2") (pintype "passive"))
      (node (ref "IC15") (pin "1") (pinfunction "OUT_1") (pintype "bidirectional"))
      (node (ref "R22") (pin "2") (pinfunction "2_2") (pintype "passive"))
      (node (ref "R24") (pin "1") (pinfunction "1_1") (pintype "passive"))
    )
    (net (code "66") (name "Net-(IC16-+IN)") (class "Default")
      (node (ref "C23") (pin "1") (pinfunction "1_1") (pintype "passive"))
      (node (ref "IC16") (pin "3") (pinfunction "+IN_3") (pintype "input"))
      (node (ref "R23") (pin "2") (pinfunction "2_2") (pintype "passive"))
    )
    (net (code "67") (name "Net-(IC17-VIN+)") (class "Default")
      (node (ref "C25") (pin "1") (pinfunction "1_1") (pintype "passive"))
      (node (ref "IC17") (pin "8") (pinfunction "VIN+_8") (pintype "bidirectional"))
      (node (ref "R25") (pin "2") (pinfunction "2_2") (pintype "passive"))
      (node (ref "R26") (pin "1") (pinfunction "1_1") (pintype "passive"))
    )
    (net (code "68") (name "Net-(IC17-VIN-)") (class "Default")
      (node (ref "C26") (pin "1") (pinfunction "1_1") (pintype "passive"))
      (node (ref "IC17") (pin "1") (pinfunction "VIN-_1") (pintype "bidirectional"))
      (node (ref "R28") (pin "2") (pinfunction "2_2") (pintype "passive"))
      (node (ref "R30") (pin "1") (pinfunction "1_1") (pintype "passive"))
    )
    (net (code "69") (name "Net-(IC17-VOUT+)") (class "Default")
      (node (ref "C26") (pin "2") (pinfunction "2_2") (pintype "passive"))
      (node (ref "IC17") (pin "4") (pinfunction "VOUT+_4") (pintype "bidirectional"))
      (node (ref "R29") (pin "2") (pinfunction "2_2") (pintype "passive"))
    )
    (net (code "70") (name "Net-(IC17-VOUT-)") (class "Default")
      (node (ref "C25") (pin "2") (pinfunction "2_2") (pintype "passive"))
      (node (ref "IC17") (pin "5") (pinfunction "VOUT-_5") (pintype "bidirectional"))
      (node (ref "R27") (pin "1") (pinfunction "1_1") (pintype "passive"))
    )
    (net (code "71") (name "Net-(IC18-VIN+)") (class "Default")
      (node (ref "C28") (pin "1") (pinfunction "1_1") (pintype "passive"))
      (node (ref "IC18") (pin "8") (pinfunction "VIN+_8") (pintype "bidirectional"))
      (node (ref "R31") (pin "2") (pinfunction "2_2") (pintype "passive"))
      (node (ref "R32") (pin "1") (pinfunction "1_1") (pintype "passive"))
    )
    (net (code "72") (name "Net-(IC18-VIN-)") (class "Default")
      (node (ref "C29") (pin "1") (pinfunction "1_1") (pintype "passive"))
      (node (ref "IC18") (pin "1") (pinfunction "VIN-_1") (pintype "bidirectional"))
      (node (ref "R34") (pin "2") (pinfunction "2_2") (pintype "passive"))
      (node (ref "R36") (pin "1") (pinfunction "1_1") (pintype "passive"))
    )
    (net (code "73") (name "Net-(IC18-VOUT+)") (class "Default")
      (node (ref "C29") (pin "2") (pinfunction "2_2") (pintype "passive"))
      (node (ref "IC18") (pin "4") (pinfunction "VOUT+_4") (pintype "bidirectional"))
      (node (ref "R35") (pin "2") (pinfunction "2_2") (pintype "passive"))
    )
    (net (code "74") (name "Net-(IC18-VOUT-)") (class "Default")
      (node (ref "C28") (pin "2") (pinfunction "2_2") (pintype "passive"))
      (node (ref "IC18") (pin "5") (pinfunction "VOUT-_5") (pintype "bidirectional"))
      (node (ref "R33") (pin "1") (pinfunction "1_1") (pintype "passive"))
    )
    (net (code "75") (name "Net-(IC19-VIN+)") (class "Default")
      (node (ref "C31") (pin "1") (pinfunction "1_1") (pintype "passive"))
      (node (ref "IC19") (pin "8") (pinfunction "VIN+_8") (pintype "bidirectional"))
      (node (ref "R37") (pin "2") (pinfunction "2_2") (pintype "passive"))
      (node (ref "R38") (pin "1") (pinfunction "1_1") (pintype "passive"))
    )
    (net (code "76") (name "Net-(IC19-VIN-)") (class "Default")
      (node (ref "C32") (pin "1") (pinfunction "1_1") (pintype "passive"))
      (node (ref "IC19") (pin "1") (pinfunction "VIN-_1") (pintype "bidirectional"))
      (node (ref "R40") (pin "2") (pinfunction "2_2") (pintype "passive"))
      (node (ref "R42") (pin "1") (pinfunction "1_1") (pintype "passive"))
    )
    (net (code "77") (name "Net-(IC19-VOUT+)") (class "Default")
      (node (ref "C32") (pin "2") (pinfunction "2_2") (pintype "passive"))
      (node (ref "IC19") (pin "4") (pinfunction "VOUT+_4") (pintype "bidirectional"))
      (node (ref "R41") (pin "2") (pinfunction "2_2") (pintype "passive"))
    )
    (net (code "78") (name "Net-(IC19-VOUT-)") (class "Default")
      (node (ref "C31") (pin "2") (pinfunction "2_2") (pintype "passive"))
      (node (ref "IC19") (pin "5") (pinfunction "VOUT-_5") (pintype "bidirectional"))
      (node (ref "R39") (pin "1") (pinfunction "1_1") (pintype "passive"))
    )
    (net (code "79") (name "Net-(IC20-VIN+)") (class "Default")
      (node (ref "C34") (pin "1") (pinfunction "1_1") (pintype "passive"))
      (node (ref "IC20") (pin "8") (pinfunction "VIN+_8") (pintype "bidirectional"))
      (node (ref "R43") (pin "2") (pinfunction "2_2") (pintype "passive"))
      (node (ref "R44") (pin "1") (pinfunction "1_1") (pintype "passive"))
    )
    (net (code "80") (name "Net-(IC20-VIN-)") (class "Default")
      (node (ref "C35") (pin "1") (pinfunction "1_1") (pintype "passive"))
      (node (ref "IC20") (pin "1") (pinfunction "VIN-_1") (pintype "bidirectional"))
      (node (ref "R46") (pin "2") (pinfunction "2_2") (pintype "passive"))
      (node (ref "R48") (pin "1") (pinfunction "1_1") (pintype "passive"))
    )
    (net (code "81") (name "Net-(IC20-VOUT+)") (class "Default")
      (node (ref "C35") (pin "2") (pinfunction "2_2") (pintype "passive"))
      (node (ref "IC20") (pin "4") (pinfunction "VOUT+_4") (pintype "bidirectional"))
      (node (ref "R47") (pin "2") (pinfunction "2_2") (pintype "passive"))
    )
    (net (code "82") (name "Net-(IC20-VOUT-)") (class "Default")
      (node (ref "C34") (pin "2") (pinfunction "2_2") (pintype "passive"))
      (node (ref "IC20") (pin "5") (pinfunction "VOUT-_5") (pintype "bidirectional"))
      (node (ref "R45") (pin "1") (pinfunction "1_1") (pintype "passive"))
    )
    (net (code "83") (name "Net-(IC21-VIN+)") (class "Default")
      (node (ref "C37") (pin "1") (pinfunction "1_1") (pintype "passive"))
      (node (ref "IC21") (pin "8") (pinfunction "VIN+_8") (pintype "bidirectional"))
      (node (ref "R49") (pin "2") (pinfunction "2_2") (pintype "passive"))
      (node (ref "R50") (pin "1") (pinfunction "1_1") (pintype "passive"))
    )
    (net (code "84") (name "Net-(IC21-VIN-)") (class "Default")
      (node (ref "C38") (pin "1") (pinfunction "1_1") (pintype "passive"))
      (node (ref "IC21") (pin "1") (pinfunction "VIN-_1") (pintype "bidirectional"))
      (node (ref "R52") (pin "2") (pinfunction "2_2") (pintype "passive"))
      (node (ref "R54") (pin "1") (pinfunction "1_1") (pintype "passive"))
    )
    (net (code "85") (name "Net-(IC21-VOUT+)") (class "Default")
      (node (ref "C38") (pin "2") (pinfunction "2_2") (pintype "passive"))
      (node (ref "IC21") (pin "4") (pinfunction "VOUT+_4") (pintype "bidirectional"))
      (node (ref "R53") (pin "2") (pinfunction "2_2") (pintype "passive"))
    )
    (net (code "86") (name "Net-(IC21-VOUT-)") (class "Default")
      (node (ref "C37") (pin "2") (pinfunction "2_2") (pintype "passive"))
      (node (ref "IC21") (pin "5") (pinfunction "VOUT-_5") (pintype "bidirectional"))
      (node (ref "R51") (pin "1") (pinfunction "1_1") (pintype "passive"))
    )
    (net (code "87") (name "Net-(IC22-VIN+)") (class "Default")
      (node (ref "C40") (pin "1") (pinfunction "1_1") (pintype "passive"))
      (node (ref "IC22") (pin "8") (pinfunction "VIN+_8") (pintype "bidirectional"))
      (node (ref "R55") (pin "2") (pinfunction "2_2") (pintype "passive"))
      (node (ref "R56") (pin "1") (pinfunction "1_1") (pintype "passive"))
    )
    (net (code "88") (name "Net-(IC22-VIN-)") (class "Default")
      (node (ref "C41") (pin "1") (pinfunction "1_1") (pintype "passive"))
      (node (ref "IC22") (pin "1") (pinfunction "VIN-_1") (pintype "bidirectional"))
      (node (ref "R58") (pin "2") (pinfunction "2_2") (pintype "passive"))
      (node (ref "R60") (pin "1") (pinfunction "1_1") (pintype "passive"))
    )
    (net (code "89") (name "Net-(IC22-VOUT+)") (class "Default")
      (node (ref "C41") (pin "2") (pinfunction "2_2") (pintype "passive"))
      (node (ref "IC22") (pin "4") (pinfunction "VOUT+_4") (pintype "bidirectional"))
      (node (ref "R59") (pin "2") (pinfunction "2_2") (pintype "passive"))
    )
    (net (code "90") (name "Net-(IC22-VOUT-)") (class "Default")
      (node (ref "C40") (pin "2") (pinfunction "2_2") (pintype "passive"))
      (node (ref "IC22") (pin "5") (pinfunction "VOUT-_5") (pintype "bidirectional"))
      (node (ref "R57") (pin "1") (pinfunction "1_1") (pintype "passive"))
    )
    (net (code "91") (name "Net-(IC23-VIN+)") (class "Default")
      (node (ref "C43") (pin "1") (pinfunction "1_1") (pintype "passive"))
      (node (ref "IC23") (pin "8") (pinfunction "VIN+_8") (pintype "bidirectional"))
      (node (ref "R61") (pin "2") (pinfunction "2_2") (pintype "passive"))
      (node (ref "R62") (pin "1") (pinfunction "1_1") (pintype "passive"))
    )
    (net (code "92") (name "Net-(IC23-VIN-)") (class "Default")
      (node (ref "C44") (pin "1") (pinfunction "1_1") (pintype "passive"))
      (node (ref "IC23") (pin "1") (pinfunction "VIN-_1") (pintype "bidirectional"))
      (node (ref "R64") (pin "2") (pinfunction "2_2") (pintype "passive"))
      (node (ref "R66") (pin "1") (pinfunction "1_1") (pintype "passive"))
    )
    (net (code "93") (name "Net-(IC23-VOUT+)") (class "Default")
      (node (ref "C44") (pin "2") (pinfunction "2_2") (pintype "passive"))
      (node (ref "IC23") (pin "4") (pinfunction "VOUT+_4") (pintype "bidirectional"))
      (node (ref "R65") (pin "2") (pinfunction "2_2") (pintype "passive"))
    )
    (net (code "94") (name "Net-(IC23-VOUT-)") (class "Default")
      (node (ref "C43") (pin "2") (pinfunction "2_2") (pintype "passive"))
      (node (ref "IC23") (pin "5") (pinfunction "VOUT-_5") (pintype "bidirectional"))
      (node (ref "R63") (pin "1") (pinfunction "1_1") (pintype "passive"))
    )
    (net (code "95") (name "Net-(IC24-VIN+)") (class "Default")
      (node (ref "C46") (pin "1") (pinfunction "1_1") (pintype "passive"))
      (node (ref "IC24") (pin "8") (pinfunction "VIN+_8") (pintype "bidirectional"))
      (node (ref "R67") (pin "2") (pinfunction "2_2") (pintype "passive"))
      (node (ref "R68") (pin "1") (pinfunction "1_1") (pintype "passive"))
    )
    (net (code "96") (name "Net-(IC24-VIN-)") (class "Default")
      (node (ref "C47") (pin "1") (pinfunction "1_1") (pintype "passive"))
      (node (ref "IC24") (pin "1") (pinfunction "VIN-_1") (pintype "bidirectional"))
      (node (ref "R70") (pin "2") (pinfunction "2_2") (pintype "passive"))
      (node (ref "R72") (pin "1") (pinfunction "1_1") (pintype "passive"))
    )
    (net (code "97") (name "Net-(IC24-VOUT+)") (class "Default")
      (node (ref "C47") (pin "2") (pinfunction "2_2") (pintype "passive"))
      (node (ref "IC24") (pin "4") (pinfunction "VOUT+_4") (pintype "bidirectional"))
      (node (ref "R71") (pin "2") (pinfunction "2_2") (pintype "passive"))
    )
    (net (code "98") (name "Net-(IC24-VOUT-)") (class "Default")
      (node (ref "C46") (pin "2") (pinfunction "2_2") (pintype "passive"))
      (node (ref "IC24") (pin "5") (pinfunction "VOUT-_5") (pintype "bidirectional"))
      (node (ref "R69") (pin "1") (pinfunction "1_1") (pintype "passive"))
    )
    (net (code "99") (name "Net-(IC25-C)") (class "Default")
      (node (ref "IC25") (pin "6") (pinfunction "C_6") (pintype "passive"))
      (node (ref "R74") (pin "1") (pinfunction "1_1") (pintype "passive"))
    )
    (net (code "100") (name "Net-(IC25-C1)") (class "Default")
      (node (ref "IC25") (pin "8") (pinfunction "C1_8") (pintype "passive"))
      (node (ref "R73") (pin "1") (pinfunction "1_1") (pintype "passive"))
    )
    (net (code "101") (name "Net-(U1-IN-)") (class "Default")
      (node (ref "R78") (pin "1") (pinfunction "1_1") (pintype "passive"))
      (node (ref "U1") (pin "2") (pinfunction "IN-_2") (pintype "input"))
      (node (ref "U1") (pin "6") (pinfunction "OUTPUT_6") (pintype "output"))
    )
    (net (code "102") (name "Net-(U2-IN+)") (class "Default")
      (node (ref "R75") (pin "2") (pinfunction "2_2") (pintype "passive"))
      (node (ref "U2") (pin "3") (pinfunction "IN+_3") (pintype "input"))
    )
    (net (code "103") (name "Net-(U2-IN-)") (class "Default")
      (node (ref "C51") (pin "1") (pinfunction "1_1") (pintype "passive"))
      (node (ref "R76") (pin "1") (pinfunction "1_1") (pintype "passive"))
      (node (ref "U2") (pin "2") (pinfunction "IN-_2") (pintype "input"))
    )
    (net (code "104") (name "Net-(U2-OUTPUT)") (class "Default")
      (node (ref "C51") (pin "2") (pinfunction "2_2") (pintype "passive"))
      (node (ref "R77") (pin "1") (pinfunction "1_1") (pintype "passive"))
      (node (ref "U2") (pin "6") (pinfunction "OUTPUT_6") (pintype "output"))
    )
    (net (code "105") (name "Net-(U3-~{PWDN1})") (class "Default")
      (node (ref "SJ1") (pin "2") (pinfunction "2_2") (pintype "passive"))
      (node (ref "U3") (pin "35") (pinfunction "~{PWDN8}_35") (pintype "input"))
      (node (ref "U3") (pin "36") (pinfunction "~{PWDN7}_36") (pintype "input"))
      (node (ref "U3") (pin "37") (pinfunction "~{PWDN6}_37") (pintype "input"))
      (node (ref "U3") (pin "38") (pinfunction "~{PWDN5}_38") (pintype "input"))
      (node (ref "U3") (pin "39") (pinfunction "~{PWDN4}_39") (pintype "input"))
      (node (ref "U3") (pin "40") (pinfunction "~{PWDN3}_40") (pintype "input"))
      (node (ref "U3") (pin "41") (pinfunction "~{PWDN2}_41") (pintype "input"))
      (node (ref "U3") (pin "42") (pinfunction "~{PWDN1}_42") (pintype "input"))
    )
    (net (code "106") (name "S1") (class "Default")
      (node (ref "C3") (pin "2") (pinfunction "2_2") (pintype "passive"))
      (node (ref "IC3") (pin "1") (pinfunction "OUT_1") (pintype "output"))
      (node (ref "IC3") (pin "4") (pinfunction "-IN_4") (pintype "input"))
      (node (ref "R25") (pin "1") (pinfunction "1_1") (pintype "passive"))
    )
    (net (code "107") (name "S2") (class "Default")
      (node (ref "C6") (pin "2") (pinfunction "2_2") (pintype "passive"))
      (node (ref "IC4") (pin "1") (pinfunction "OUT_1") (pintype "output"))
      (node (ref "IC4") (pin "4") (pinfunction "-IN_4") (pintype "input"))
      (node (ref "R31") (pin "1") (pinfunction "1_1") (pintype "passive"))
    )
    (net (code "108") (name "S3") (class "Default")
      (node (ref "C9") (pin "2") (pinfunction "2_2") (pintype "passive"))
      (node (ref "IC6") (pin "1") (pinfunction "OUT_1") (pintype "output"))
      (node (ref "IC6") (pin "4") (pinfunction "-IN_4") (pintype "input"))
      (node (ref "R37") (pin "1") (pinfunction "1_1") (pintype "passive"))
    )
    (net (code "109") (name "S4") (class "Default")
      (node (ref "C12") (pin "2") (pinfunction "2_2") (pintype "passive"))
      (node (ref "IC8") (pin "1") (pinfunction "OUT_1") (pintype "output"))
      (node (ref "IC8") (pin "4") (pinfunction "-IN_4") (pintype "input"))
      (node (ref "R43") (pin "1") (pinfunction "1_1") (pintype "passive"))
    )
    (net (code "110") (name "S5") (class "Default")
      (node (ref "C15") (pin "2") (pinfunction "2_2") (pintype "passive"))
      (node (ref "IC10") (pin "1") (pinfunction "OUT_1") (pintype "output"))
      (node (ref "IC10") (pin "4") (pinfunction "-IN_4") (pintype "input"))
      (node (ref "R49") (pin "1") (pinfunction "1_1") (pintype "passive"))
    )
    (net (code "111") (name "S6") (class "Default")
      (node (ref "C18") (pin "2") (pinfunction "2_2") (pintype "passive"))
      (node (ref "IC12") (pin "1") (pinfunction "OUT_1") (pintype "output"))
      (node (ref "IC12") (pin "4") (pinfunction "-IN_4") (pintype "input"))
      (node (ref "R55") (pin "1") (pinfunction "1_1") (pintype "passive"))
    )
    (net (code "112") (name "S7") (class "Default")
      (node (ref "C21") (pin "2") (pinfunction "2_2") (pintype "passive"))
      (node (ref "IC14") (pin "1") (pinfunction "OUT_1") (pintype "output"))
      (node (ref "IC14") (pin "4") (pinfunction "-IN_4") (pintype "input"))
      (node (ref "R61") (pin "1") (pinfunction "1_1") (pintype "passive"))
    )
    (net (code "113") (name "S8") (class "Default")
      (node (ref "C24") (pin "2") (pinfunction "2_2") (pintype "passive"))
      (node (ref "IC16") (pin "1") (pinfunction "OUT_1") (pintype "output"))
      (node (ref "IC16") (pin "4") (pinfunction "-IN_4") (pintype "input"))
      (node (ref "R67") (pin "1") (pinfunction "1_1") (pintype "passive"))
    )
    (net (code "114") (name "SCLK") (class "Default")
      (node (ref "JP2") (pin "12") (pinfunction "12_12") (pintype "passive"))
      (node (ref "U3") (pin "28") (pinfunction "SCLK_28") (pintype "input"))
    )
    (net (code "115") (name "SYNC") (class "Default")
      (node (ref "JP2") (pin "2") (pinfunction "2_2") (pintype "passive"))
      (node (ref "U3") (pin "11") (pinfunction "~{SYNC}_11") (pintype "input"))
    )
    (net (code "116") (name "VCOM") (class "Default")
      (node (ref "C27") (pin "1") (pinfunction "1_1") (pintype "passive"))
      (node (ref "C30") (pin "1") (pinfunction "1_1") (pintype "passive"))
      (node (ref "C33") (pin "1") (pinfunction "1_1") (pintype "passive"))
      (node (ref "C36") (pin "1") (pinfunction "1_1") (pintype "passive"))
      (node (ref "C39") (pin "1") (pinfunction "1_1") (pintype "passive"))
      (node (ref "C42") (pin "1") (pinfunction "1_1") (pintype "passive"))
      (node (ref "C45") (pin "1") (pinfunction "1_1") (pintype "passive"))
      (node (ref "C48") (pin "1") (pinfunction "1_1") (pintype "passive"))
      (node (ref "IC17") (pin "2") (pinfunction "VOCM_2") (pintype "bidirectional"))
      (node (ref "IC18") (pin "2") (pinfunction "VOCM_2") (pintype "bidirectional"))
      (node (ref "IC19") (pin "2") (pinfunction "VOCM_2") (pintype "bidirectional"))
      (node (ref "IC20") (pin "2") (pinfunction "VOCM_2") (pintype "bidirectional"))
      (node (ref "IC21") (pin "2") (pinfunction "VOCM_2") (pintype "bidirectional"))
      (node (ref "IC22") (pin "2") (pinfunction "VOCM_2") (pintype "bidirectional"))
      (node (ref "IC23") (pin "2") (pinfunction "VOCM_2") (pintype "bidirectional"))
      (node (ref "IC24") (pin "2") (pinfunction "VOCM_2") (pintype "bidirectional"))
      (node (ref "R78") (pin "2") (pinfunction "2_2") (pintype "passive"))
    )
    (net (code "117") (name "VCOMM") (class "Default")
      (node (ref "C54") (pin "1") (pinfunction "1_1") (pintype "passive"))
      (node (ref "U1") (pin "3") (pinfunction "IN+_3") (pintype "input"))
      (node (ref "U3") (pin "55") (pinfunction "VCOM_55") (pintype "power_in"))
    )
    (net (code "118") (name "VREFP") (class "Default")
      (node (ref "C52") (pin "1") (pinfunction "1_1") (pintype "passive"))
      (node (ref "C53") (pin "1") (pinfunction "1_1") (pintype "passive"))
      (node (ref "R76") (pin "2") (pinfunction "2_2") (pintype "passive"))
      (node (ref "R77") (pin "2") (pinfunction "2_2") (pintype "passive"))
      (node (ref "U3") (pin "56") (pinfunction "VREFP_56") (pintype "power_in"))
    )
    (net (code "119") (name "unconnected-(IC17-ENABLE-Pad7)") (class "Default")
      (node (ref "IC17") (pin "7") (pinfunction "ENABLE_7") (pintype "bidirectional"))
    )
    (net (code "120") (name "unconnected-(IC18-ENABLE-Pad7)") (class "Default")
      (node (ref "IC18") (pin "7") (pinfunction "ENABLE_7") (pintype "bidirectional"))
    )
    (net (code "121") (name "unconnected-(IC19-ENABLE-Pad7)") (class "Default")
      (node (ref "IC19") (pin "7") (pinfunction "ENABLE_7") (pintype "bidirectional"))
    )
    (net (code "122") (name "unconnected-(IC20-ENABLE-Pad7)") (class "Default")
      (node (ref "IC20") (pin "7") (pinfunction "ENABLE_7") (pintype "bidirectional"))
    )
    (net (code "123") (name "unconnected-(IC21-ENABLE-Pad7)") (class "Default")
      (node (ref "IC21") (pin "7") (pinfunction "ENABLE_7") (pintype "bidirectional"))
    )
    (net (code "124") (name "unconnected-(IC22-ENABLE-Pad7)") (class "Default")
      (node (ref "IC22") (pin "7") (pinfunction "ENABLE_7") (pintype "bidirectional"))
    )
    (net (code "125") (name "unconnected-(IC23-ENABLE-Pad7)") (class "Default")
      (node (ref "IC23") (pin "7") (pinfunction "ENABLE_7") (pintype "bidirectional"))
    )
    (net (code "126") (name "unconnected-(IC24-ENABLE-Pad7)") (class "Default")
      (node (ref "IC24") (pin "7") (pinfunction "ENABLE_7") (pintype "bidirectional"))
    )
    (net (code "127") (name "unconnected-(IC25-NC-Pad1)") (class "Default")
      (node (ref "IC25") (pin "1") (pinfunction "NC_1") (pintype "no_connect"))
    )
    (net (code "128") (name "unconnected-(IC25-NC-Pad2)") (class "Default")
      (node (ref "IC25") (pin "2") (pinfunction "NC_2") (pintype "no_connect"))
    )
    (net (code "129") (name "unconnected-(IC25-NC-Pad3)") (class "Default")
      (node (ref "IC25") (pin "3") (pinfunction "NC_3") (pintype "no_connect"))
    )
    (net (code "130") (name "unconnected-(IC25-NC-Pad5)") (class "Default")
      (node (ref "IC25") (pin "5") (pinfunction "NC_5") (pintype "no_connect"))
    )
    (net (code "131") (name "unconnected-(IC25-NC-Pad7)") (class "Default")
      (node (ref "IC25") (pin "7") (pinfunction "NC_7") (pintype "no_connect"))
    )
    (net (code "132") (name "unconnected-(U1-NC-Pad8)") (class "Default")
      (node (ref "U1") (pin "8") (pinfunction "NC_8") (pintype "passive"))
    )
    (net (code "133") (name "unconnected-(U1-NC_2-Pad1)") (class "Default")
      (node (ref "U1") (pin "1") (pinfunction "NC_2_1") (pintype "passive"))
    )
    (net (code "134") (name "unconnected-(U1-NC_3-Pad5)") (class "Default")
      (node (ref "U1") (pin "5") (pinfunction "NC_3_5") (pintype "passive"))
    )
    (net (code "135") (name "unconnected-(U2-NC-Pad8)") (class "Default")
      (node (ref "U2") (pin "8") (pinfunction "NC_8") (pintype "passive"))
    )
    (net (code "136") (name "unconnected-(U2-NC_2-Pad1)") (class "Default")
      (node (ref "U2") (pin "1") (pinfunction "NC_2_1") (pintype "passive"))
    )
    (net (code "137") (name "unconnected-(U2-NC_3-Pad5)") (class "Default")
      (node (ref "U2") (pin "5") (pinfunction "NC_3_5") (pintype "passive"))
    )
    (net (code "138") (name "unconnected-(U3-NC-Pad33)") (class "Default")
      (node (ref "U3") (pin "33") (pinfunction "NC_33") (pintype "no_connect"))
    )
  )
)
